# Beta24_mix.net
KiCad netlist of a schematic drawn in EAGLE
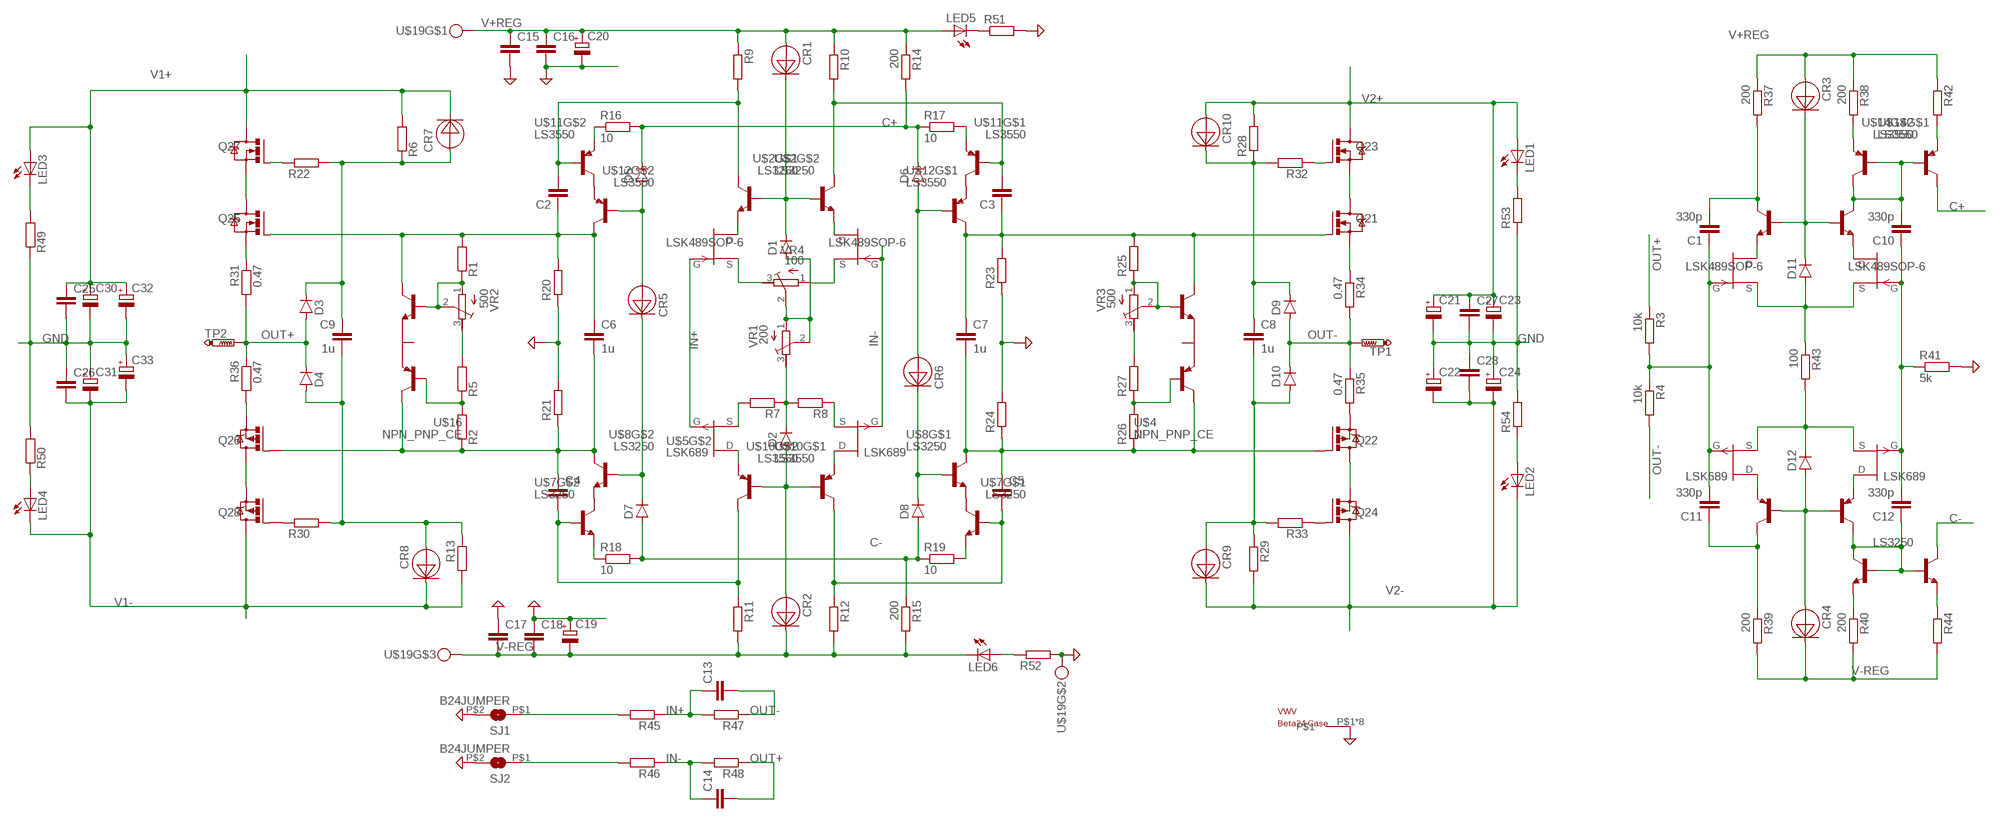
[diagram p0: schematic, sheet 1]
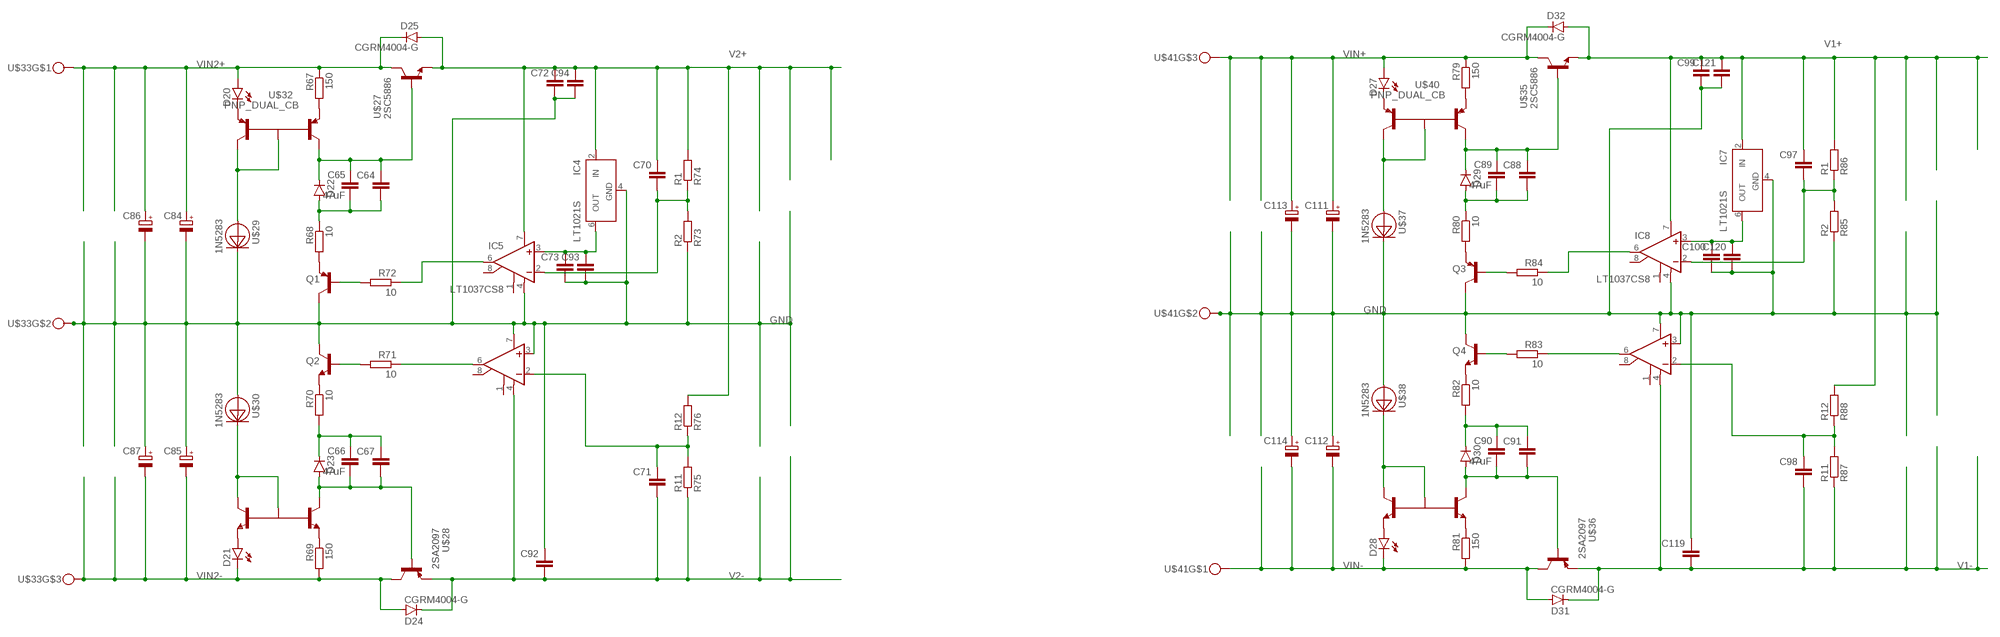
[diagram p1: schematic, sheet 2]

(export (version "E")
  (design (tool "Eeschema 10.0.6"))
  (components
    (comp (ref "C64")
      (value "C-EUC0805")
      (footprint "eagle-import:C0805")
      (libsource (lib "eagle-import") (part "C-EUC0805"))
    )
    (comp (ref "C65")
      (value "47uF")
      (footprint "eagle-import:C1206")
      (libsource (lib "eagle-import") (part "C-EUC1206"))
    )
    (comp (ref "C66")
      (value "47uF")
      (footprint "eagle-import:C1206")
      (libsource (lib "eagle-import") (part "C-EUC1206"))
    )
    (comp (ref "C67")
      (value "C-EUC0805")
      (footprint "eagle-import:C0805")
      (libsource (lib "eagle-import") (part "C-EUC0805"))
    )
    (comp (ref "C70")
      (value "C-EUC0805")
      (footprint "eagle-import:C0805")
      (libsource (lib "eagle-import") (part "C-EUC0805"))
    )
    (comp (ref "C71")
      (value "C-EUC0805")
      (footprint "eagle-import:C0805")
      (libsource (lib "eagle-import") (part "C-EUC0805"))
    )
    (comp (ref "C72")
      (value "C-EUC0805")
      (footprint "eagle-import:C0805")
      (libsource (lib "eagle-import") (part "C-EUC0805"))
    )
    (comp (ref "C73")
      (value "C-EUC0805")
      (footprint "eagle-import:C0805")
      (libsource (lib "eagle-import") (part "C-EUC0805"))
    )
    (comp (ref "C84")
      (value "CPOL-EUG")
      (footprint "eagle-import:PANASONIC_G")
      (libsource (lib "eagle-import") (part "CPOL-EUG"))
    )
    (comp (ref "C85")
      (value "CPOL-EUG")
      (footprint "eagle-import:PANASONIC_G")
      (libsource (lib "eagle-import") (part "CPOL-EUG"))
    )
    (comp (ref "C86")
      (value "CPOL-EUG")
      (footprint "eagle-import:PANASONIC_G")
      (libsource (lib "eagle-import") (part "CPOL-EUG"))
    )
    (comp (ref "C87")
      (value "CPOL-EUG")
      (footprint "eagle-import:PANASONIC_G")
      (libsource (lib "eagle-import") (part "CPOL-EUG"))
    )
    (comp (ref "C88")
      (value "C-EUC0805")
      (footprint "eagle-import:C0805")
      (libsource (lib "eagle-import") (part "C-EUC0805"))
    )
    (comp (ref "C89")
      (value "47uF")
      (footprint "eagle-import:C1206")
      (libsource (lib "eagle-import") (part "C-EUC1206"))
    )
    (comp (ref "C90")
      (value "47uF")
      (footprint "eagle-import:C1206")
      (libsource (lib "eagle-import") (part "C-EUC1206"))
    )
    (comp (ref "C91")
      (value "C-EUC0805")
      (footprint "eagle-import:C0805")
      (libsource (lib "eagle-import") (part "C-EUC0805"))
    )
    (comp (ref "C92")
      (value "C-EUC0805")
      (footprint "eagle-import:C0805")
      (libsource (lib "eagle-import") (part "C-EUC0805"))
    )
    (comp (ref "C93")
      (value "C-EUC0805")
      (footprint "eagle-import:C0805")
      (libsource (lib "eagle-import") (part "C-EUC0805"))
    )
    (comp (ref "C94")
      (value "C-EUC0805")
      (footprint "eagle-import:C0805")
      (libsource (lib "eagle-import") (part "C-EUC0805"))
    )
    (comp (ref "C97")
      (value "C-EUC0805")
      (footprint "eagle-import:C0805")
      (libsource (lib "eagle-import") (part "C-EUC0805"))
    )
    (comp (ref "C98")
      (value "C-EUC0805")
      (footprint "eagle-import:C0805")
      (libsource (lib "eagle-import") (part "C-EUC0805"))
    )
    (comp (ref "C99")
      (value "C-EUC0805")
      (footprint "eagle-import:C0805")
      (libsource (lib "eagle-import") (part "C-EUC0805"))
    )
    (comp (ref "C100")
      (value "C-EUC0805")
      (footprint "eagle-import:C0805")
      (libsource (lib "eagle-import") (part "C-EUC0805"))
    )
    (comp (ref "C111")
      (value "CPOL-EUG")
      (footprint "eagle-import:PANASONIC_G")
      (libsource (lib "eagle-import") (part "CPOL-EUG"))
    )
    (comp (ref "C112")
      (value "CPOL-EUG")
      (footprint "eagle-import:PANASONIC_G")
      (libsource (lib "eagle-import") (part "CPOL-EUG"))
    )
    (comp (ref "C113")
      (value "CPOL-EUG")
      (footprint "eagle-import:PANASONIC_G")
      (libsource (lib "eagle-import") (part "CPOL-EUG"))
    )
    (comp (ref "C114")
      (value "CPOL-EUG")
      (footprint "eagle-import:PANASONIC_G")
      (libsource (lib "eagle-import") (part "CPOL-EUG"))
    )
    (comp (ref "C119")
      (value "C-EUC0805")
      (footprint "eagle-import:C0805")
      (libsource (lib "eagle-import") (part "C-EUC0805"))
    )
    (comp (ref "C120")
      (value "C-EUC0805")
      (footprint "eagle-import:C0805")
      (libsource (lib "eagle-import") (part "C-EUC0805"))
    )
    (comp (ref "C121")
      (value "C-EUC0805")
      (footprint "eagle-import:C0805")
      (libsource (lib "eagle-import") (part "C-EUC0805"))
    )
    (comp (ref "D20")
      (value "LEDVWV1206")
      (footprint "eagle-import:LED_SML1206")
      (libsource (lib "eagle-import") (part "LEDVWV1206"))
    )
    (comp (ref "D21")
      (value "LEDVWV1206")
      (footprint "eagle-import:LED_SML1206")
      (libsource (lib "eagle-import") (part "LEDVWV1206"))
    )
    (comp (ref "D22")
      (value "TZMC10")
      (footprint "eagle-import:SOD80C")
      (libsource (lib "eagle-import") (part "DIODE-SOD80C"))
    )
    (comp (ref "D23")
      (value "TZAMC10")
      (footprint "eagle-import:SOD80C")
      (libsource (lib "eagle-import") (part "DIODE-SOD80C"))
    )
    (comp (ref "D24")
      (value "CGRM4004-G")
      (footprint "eagle-import:SOD-123_MINI-SMA")
      (libsource (lib "eagle-import") (part "CGRM400-G4"))
    )
    (comp (ref "D25")
      (value "CGRM4004-G")
      (footprint "eagle-import:SOD-123_MINI-SMA")
      (libsource (lib "eagle-import") (part "CGRM400-G4"))
    )
    (comp (ref "D27")
      (value "LEDVWV1206")
      (footprint "eagle-import:LED_SML1206")
      (libsource (lib "eagle-import") (part "LEDVWV1206"))
    )
    (comp (ref "D28")
      (value "LEDVWV1206")
      (footprint "eagle-import:LED_SML1206")
      (libsource (lib "eagle-import") (part "LEDVWV1206"))
    )
    (comp (ref "D29")
      (value "TZMC10")
      (footprint "eagle-import:SOD80C")
      (libsource (lib "eagle-import") (part "DIODE-SOD80C"))
    )
    (comp (ref "D30")
      (value "TZAMC10")
      (footprint "eagle-import:SOD80C")
      (libsource (lib "eagle-import") (part "DIODE-SOD80C"))
    )
    (comp (ref "D31")
      (value "CGRM4004-G")
      (footprint "eagle-import:SOD-123_MINI-SMA")
      (libsource (lib "eagle-import") (part "CGRM400-G4"))
    )
    (comp (ref "D32")
      (value "CGRM4004-G")
      (footprint "eagle-import:SOD-123_MINI-SMA")
      (libsource (lib "eagle-import") (part "CGRM400-G4"))
    )
    (comp (ref "IC4")
      (value "LT1021S")
      (footprint "eagle-import:SOIC8")
      (fields (field (name "MPN") "LT1021DCS8-10#PBF"))
      (libsource (lib "eagle-import") (part "LT1021S"))
    )
    (comp (ref "IC5")
      (value "LT1037CS8")
      (footprint "eagle-import:SOIC8")
      (libsource (lib "eagle-import") (part "LT10S837C"))
    )
    (comp (ref "IC6")
      (value "LT1037CS8")
      (footprint "eagle-import:SOIC8")
      (libsource (lib "eagle-import") (part "LT10S837C"))
    )
    (comp (ref "IC7")
      (value "LT1021S")
      (footprint "eagle-import:SOIC8")
      (fields (field (name "MPN") "LT1021DCS8-10#PBF"))
      (libsource (lib "eagle-import") (part "LT1021S"))
    )
    (comp (ref "IC8")
      (value "LT1037CS8")
      (footprint "eagle-import:SOIC8")
      (libsource (lib "eagle-import") (part "LT10S837C"))
    )
    (comp (ref "IC9")
      (value "LT1037CS8")
      (footprint "eagle-import:SOIC8")
      (libsource (lib "eagle-import") (part "LT10S837C"))
    )
    (comp (ref "Q1")
      (value "TRANSISTOR_BC857C-PNP-SOT23-BEC")
      (footprint "eagle-import:TRANSISTOR_SOT23-BEC")
      (libsource (lib "eagle-import") (part "TRANSISTOR_-PNP-SOT23-BECBC857C"))
    )
    (comp (ref "Q2")
      (value "TRANSISTOR_BC847CLT1-NPN-SOT23-BEC")
      (footprint "eagle-import:TRANSISTOR_SOT23-BEC")
      (libsource (lib "eagle-import") (part "TRANSISTOR_-NPN-SOT23-BECBC847CLT1"))
    )
    (comp (ref "Q3")
      (value "TRANSISTOR_BC857C-PNP-SOT23-BEC")
      (footprint "eagle-import:TRANSISTOR_SOT23-BEC")
      (libsource (lib "eagle-import") (part "TRANSISTOR_-PNP-SOT23-BECBC857C"))
    )
    (comp (ref "Q4")
      (value "TRANSISTOR_BC847CLT1-NPN-SOT23-BEC")
      (footprint "eagle-import:TRANSISTOR_SOT23-BEC")
      (libsource (lib "eagle-import") (part "TRANSISTOR_-NPN-SOT23-BECBC847CLT1"))
    )
    (comp (ref "R67")
      (value "150")
      (footprint "eagle-import:MINI_MELF-0204W")
      (libsource (lib "eagle-import") (part "R-EU_MELF0204W"))
    )
    (comp (ref "R68")
      (value "10")
      (footprint "eagle-import:MINI_MELF-0204W")
      (libsource (lib "eagle-import") (part "R-EU_MELF0204W"))
    )
    (comp (ref "R69")
      (value "150")
      (footprint "eagle-import:MINI_MELF-0204W")
      (libsource (lib "eagle-import") (part "R-EU_MELF0204W"))
    )
    (comp (ref "R70")
      (value "10")
      (footprint "eagle-import:MINI_MELF-0204W")
      (libsource (lib "eagle-import") (part "R-EU_MELF0204W"))
    )
    (comp (ref "R71")
      (value "10")
      (footprint "eagle-import:MINI_MELF-0204W")
      (libsource (lib "eagle-import") (part "R-EU_MELF0204W"))
    )
    (comp (ref "R72")
      (value "10")
      (footprint "eagle-import:MINI_MELF-0204W")
      (libsource (lib "eagle-import") (part "R-EU_MELF0204W"))
    )
    (comp (ref "R73")
      (value "R2")
      (footprint "eagle-import:MINI_MELF-0204W")
      (libsource (lib "eagle-import") (part "R-EU_MELF0204W"))
    )
    (comp (ref "R74")
      (value "R1")
      (footprint "eagle-import:MINI_MELF-0204W")
      (libsource (lib "eagle-import") (part "R-EU_MELF0204W"))
    )
    (comp (ref "R75")
      (value "R11")
      (footprint "eagle-import:MINI_MELF-0204W")
      (libsource (lib "eagle-import") (part "R-EU_MELF0204W"))
    )
    (comp (ref "R76")
      (value "R12")
      (footprint "eagle-import:MINI_MELF-0204W")
      (libsource (lib "eagle-import") (part "R-EU_MELF0204W"))
    )
    (comp (ref "R79")
      (value "150")
      (footprint "eagle-import:MINI_MELF-0204W")
      (libsource (lib "eagle-import") (part "R-EU_MELF0204W"))
    )
    (comp (ref "R80")
      (value "10")
      (footprint "eagle-import:MINI_MELF-0204W")
      (libsource (lib "eagle-import") (part "R-EU_MELF0204W"))
    )
    (comp (ref "R81")
      (value "150")
      (footprint "eagle-import:MINI_MELF-0204W")
      (libsource (lib "eagle-import") (part "R-EU_MELF0204W"))
    )
    (comp (ref "R82")
      (value "10")
      (footprint "eagle-import:MINI_MELF-0204W")
      (libsource (lib "eagle-import") (part "R-EU_MELF0204W"))
    )
    (comp (ref "R83")
      (value "10")
      (footprint "eagle-import:MINI_MELF-0204W")
      (libsource (lib "eagle-import") (part "R-EU_MELF0204W"))
    )
    (comp (ref "R84")
      (value "10")
      (footprint "eagle-import:MINI_MELF-0204W")
      (libsource (lib "eagle-import") (part "R-EU_MELF0204W"))
    )
    (comp (ref "R85")
      (value "R2")
      (footprint "eagle-import:MINI_MELF-0204W")
      (libsource (lib "eagle-import") (part "R-EU_MELF0204W"))
    )
    (comp (ref "R86")
      (value "R1")
      (footprint "eagle-import:MINI_MELF-0204W")
      (libsource (lib "eagle-import") (part "R-EU_MELF0204W"))
    )
    (comp (ref "R87")
      (value "R11")
      (footprint "eagle-import:MINI_MELF-0204W")
      (libsource (lib "eagle-import") (part "R-EU_MELF0204W"))
    )
    (comp (ref "R88")
      (value "R12")
      (footprint "eagle-import:MINI_MELF-0204W")
      (libsource (lib "eagle-import") (part "R-EU_MELF0204W"))
    )
    (comp (ref "U$27")
      (value "2SC5886")
      (footprint "eagle-import:NEW-PWMOLD")
      (libsource (lib "eagle-import") (part "2SC5886"))
    )
    (comp (ref "U$28")
      (value "2SA2097")
      (footprint "eagle-import:NEW-PWMOLD")
      (libsource (lib "eagle-import") (part "2SA2097"))
    )
    (comp (ref "U$29")
      (value "1N5283")
      (footprint "eagle-import:SMD")
      (libsource (lib "eagle-import") (part "1N5283"))
    )
    (comp (ref "U$30")
      (value "1N5283")
      (footprint "eagle-import:SMD")
      (libsource (lib "eagle-import") (part "1N5283"))
    )
    (comp (ref "U$31")
      (value "NPN_DUAL_CBSOT-25-5")
      (footprint "eagle-import:SOT25")
      (libsource (lib "eagle-import") (part "NPN_DUAL_CBSOT-25-5"))
    )
    (comp (ref "U$32")
      (value "PNP_DUAL_CB")
      (footprint "eagle-import:SOT25")
      (libsource (lib "eagle-import") (part "PNP_DUAL_CB"))
    )
    (comp (ref "U$33")
      (value "CON-PTSM-3")
      (footprint "eagle-import:CON-PTSM-3")
      (libsource (lib "eagle-import") (part "CON-PTSM-3"))
    )
    (comp (ref "U$35")
      (value "2SC5886")
      (footprint "eagle-import:NEW-PWMOLD")
      (libsource (lib "eagle-import") (part "2SC5886"))
    )
    (comp (ref "U$36")
      (value "2SA2097")
      (footprint "eagle-import:NEW-PWMOLD")
      (libsource (lib "eagle-import") (part "2SA2097"))
    )
    (comp (ref "U$37")
      (value "1N5283")
      (footprint "eagle-import:SMD")
      (libsource (lib "eagle-import") (part "1N5283"))
    )
    (comp (ref "U$38")
      (value "1N5283")
      (footprint "eagle-import:SMD")
      (libsource (lib "eagle-import") (part "1N5283"))
    )
    (comp (ref "U$39")
      (value "NPN_DUAL_CBSOT-25-5")
      (footprint "eagle-import:SOT25")
      (libsource (lib "eagle-import") (part "NPN_DUAL_CBSOT-25-5"))
    )
    (comp (ref "U$40")
      (value "PNP_DUAL_CB")
      (footprint "eagle-import:SOT25")
      (libsource (lib "eagle-import") (part "PNP_DUAL_CB"))
    )
    (comp (ref "U$41")
      (value "CON-PTSM-3")
      (footprint "eagle-import:CON-PTSM-3")
      (libsource (lib "eagle-import") (part "CON-PTSM-3"))
    )
    (comp (ref "C1")
      (value "330p")
      (footprint "eagle-import:C1206")
      (libsource (lib "eagle-import") (part "C-EUC1206"))
    )
    (comp (ref "C2")
      (value "C-EUC1206")
      (footprint "eagle-import:C1206")
      (libsource (lib "eagle-import") (part "C-EUC1206"))
    )
    (comp (ref "C3")
      (value "C-EUC1206")
      (footprint "eagle-import:C1206")
      (libsource (lib "eagle-import") (part "C-EUC1206"))
    )
    (comp (ref "C4")
      (value "C-EUC1206")
      (footprint "eagle-import:C1206")
      (libsource (lib "eagle-import") (part "C-EUC1206"))
    )
    (comp (ref "C5")
      (value "C-EUC1206")
      (footprint "eagle-import:C1206")
      (libsource (lib "eagle-import") (part "C-EUC1206"))
    )
    (comp (ref "C6")
      (value "1u")
      (footprint "eagle-import:C1210")
      (libsource (lib "eagle-import") (part "C-EUC1210"))
    )
    (comp (ref "C7")
      (value "1u")
      (footprint "eagle-import:C1210")
      (libsource (lib "eagle-import") (part "C-EUC1210"))
    )
    (comp (ref "C8")
      (value "1u")
      (footprint "eagle-import:C1206")
      (libsource (lib "eagle-import") (part "C-EUC1206"))
    )
    (comp (ref "C9")
      (value "1u")
      (footprint "eagle-import:C1206")
      (libsource (lib "eagle-import") (part "C-EUC1206"))
    )
    (comp (ref "C10")
      (value "330p")
      (footprint "eagle-import:C1206")
      (libsource (lib "eagle-import") (part "C-EUC1206"))
    )
    (comp (ref "C11")
      (value "330p")
      (footprint "eagle-import:C1206")
      (libsource (lib "eagle-import") (part "C-EUC1206"))
    )
    (comp (ref "C12")
      (value "330p")
      (footprint "eagle-import:C1206")
      (libsource (lib "eagle-import") (part "C-EUC1206"))
    )
    (comp (ref "C13")
      (value "C-EUC1206")
      (footprint "eagle-import:C1206")
      (libsource (lib "eagle-import") (part "C-EUC1206"))
    )
    (comp (ref "C14")
      (value "C-EUC1206")
      (footprint "eagle-import:C1206")
      (libsource (lib "eagle-import") (part "C-EUC1206"))
    )
    (comp (ref "C15")
      (value "C-EUC1206")
      (footprint "eagle-import:C1206")
      (libsource (lib "eagle-import") (part "C-EUC1206"))
    )
    (comp (ref "C16")
      (value "C-EUC1206")
      (footprint "eagle-import:C1206")
      (libsource (lib "eagle-import") (part "C-EUC1206"))
    )
    (comp (ref "C17")
      (value "C-EUC1206")
      (footprint "eagle-import:C1206")
      (libsource (lib "eagle-import") (part "C-EUC1206"))
    )
    (comp (ref "C18")
      (value "C-EUC1206")
      (footprint "eagle-import:C1206")
      (libsource (lib "eagle-import") (part "C-EUC1206"))
    )
    (comp (ref "C19")
      (value "CPOL-EUG")
      (footprint "eagle-import:PANASONIC_G")
      (libsource (lib "eagle-import") (part "CPOL-EUG"))
    )
    (comp (ref "C20")
      (value "CPOL-EUG")
      (footprint "eagle-import:PANASONIC_G")
      (libsource (lib "eagle-import") (part "CPOL-EUG"))
    )
    (comp (ref "C21")
      (value "CPOL-EUG")
      (footprint "eagle-import:PANASONIC_G")
      (libsource (lib "eagle-import") (part "CPOL-EUG"))
    )
    (comp (ref "C22")
      (value "CPOL-EUG")
      (footprint "eagle-import:PANASONIC_G")
      (libsource (lib "eagle-import") (part "CPOL-EUG"))
    )
    (comp (ref "C23")
      (value "CPOL-EUG")
      (footprint "eagle-import:PANASONIC_G")
      (libsource (lib "eagle-import") (part "CPOL-EUG"))
    )
    (comp (ref "C24")
      (value "CPOL-EUG")
      (footprint "eagle-import:PANASONIC_G")
      (libsource (lib "eagle-import") (part "CPOL-EUG"))
    )
    (comp (ref "C25")
      (value "C-EUC1206")
      (footprint "eagle-import:C1206")
      (libsource (lib "eagle-import") (part "C-EUC1206"))
    )
    (comp (ref "C26")
      (value "C-EUC1206")
      (footprint "eagle-import:C1206")
      (libsource (lib "eagle-import") (part "C-EUC1206"))
    )
    (comp (ref "C27")
      (value "C-EUC1206")
      (footprint "eagle-import:C1206")
      (libsource (lib "eagle-import") (part "C-EUC1206"))
    )
    (comp (ref "C28")
      (value "C-EUC1206")
      (footprint "eagle-import:C1206")
      (libsource (lib "eagle-import") (part "C-EUC1206"))
    )
    (comp (ref "C30")
      (value "CPOL-EUG")
      (footprint "eagle-import:PANASONIC_G")
      (libsource (lib "eagle-import") (part "CPOL-EUG"))
    )
    (comp (ref "C31")
      (value "CPOL-EUG")
      (footprint "eagle-import:PANASONIC_G")
      (libsource (lib "eagle-import") (part "CPOL-EUG"))
    )
    (comp (ref "C32")
      (value "CPOL-EUG")
      (footprint "eagle-import:PANASONIC_G")
      (libsource (lib "eagle-import") (part "CPOL-EUG"))
    )
    (comp (ref "C33")
      (value "CPOL-EUG")
      (footprint "eagle-import:PANASONIC_G")
      (libsource (lib "eagle-import") (part "CPOL-EUG"))
    )
    (comp (ref "CR1")
      (value "1N5283")
      (footprint "eagle-import:SMD")
      (libsource (lib "eagle-import") (part "1N5283"))
    )
    (comp (ref "CR2")
      (value "1N5283")
      (footprint "eagle-import:SMD")
      (libsource (lib "eagle-import") (part "1N5283"))
    )
    (comp (ref "CR3")
      (value "1N5283")
      (footprint "eagle-import:SMD")
      (libsource (lib "eagle-import") (part "1N5283"))
    )
    (comp (ref "CR4")
      (value "1N5283")
      (footprint "eagle-import:SMD")
      (libsource (lib "eagle-import") (part "1N5283"))
    )
    (comp (ref "CR5")
      (value "1N5283")
      (footprint "eagle-import:SMD")
      (libsource (lib "eagle-import") (part "1N5283"))
    )
    (comp (ref "CR6")
      (value "1N5283")
      (footprint "eagle-import:SMD")
      (libsource (lib "eagle-import") (part "1N5283"))
    )
    (comp (ref "CR7")
      (value "1N5283")
      (footprint "eagle-import:SMD")
      (libsource (lib "eagle-import") (part "1N5283"))
    )
    (comp (ref "CR8")
      (value "1N5283")
      (footprint "eagle-import:SMD")
      (libsource (lib "eagle-import") (part "1N5283"))
    )
    (comp (ref "CR9")
      (value "1N5283")
      (footprint "eagle-import:SMD")
      (libsource (lib "eagle-import") (part "1N5283"))
    )
    (comp (ref "CR10")
      (value "1N5283")
      (footprint "eagle-import:SMD")
      (libsource (lib "eagle-import") (part "1N5283"))
    )
    (comp (ref "D1")
      (value "DIODE-SOD80C")
      (footprint "eagle-import:SOD80C")
      (libsource (lib "eagle-import") (part "DIODE-SOD80C"))
    )
    (comp (ref "D2")
      (value "DIODE-SOD80C")
      (footprint "eagle-import:SOD80C")
      (libsource (lib "eagle-import") (part "DIODE-SOD80C"))
    )
    (comp (ref "D3")
      (value "DIODE-SOD80C")
      (footprint "eagle-import:SOD80C")
      (libsource (lib "eagle-import") (part "DIODE-SOD80C"))
    )
    (comp (ref "D4")
      (value "DIODE-SOD80C")
      (footprint "eagle-import:SOD80C")
      (libsource (lib "eagle-import") (part "DIODE-SOD80C"))
    )
    (comp (ref "D5")
      (value "DIODE-SOD80C")
      (footprint "eagle-import:SOD80C")
      (libsource (lib "eagle-import") (part "DIODE-SOD80C"))
    )
    (comp (ref "D6")
      (value "DIODE-SOD80C")
      (footprint "eagle-import:SOD80C")
      (libsource (lib "eagle-import") (part "DIODE-SOD80C"))
    )
    (comp (ref "D7")
      (value "DIODE-SOD80C")
      (footprint "eagle-import:SOD80C")
      (libsource (lib "eagle-import") (part "DIODE-SOD80C"))
    )
    (comp (ref "D8")
      (value "DIODE-SOD80C")
      (footprint "eagle-import:SOD80C")
      (libsource (lib "eagle-import") (part "DIODE-SOD80C"))
    )
    (comp (ref "D9")
      (value "DIODE-SOD80C")
      (footprint "eagle-import:SOD80C")
      (libsource (lib "eagle-import") (part "DIODE-SOD80C"))
    )
    (comp (ref "D10")
      (value "DIODE-SOD80C")
      (footprint "eagle-import:SOD80C")
      (libsource (lib "eagle-import") (part "DIODE-SOD80C"))
    )
    (comp (ref "D11")
      (value "DIODE-SOD80C")
      (footprint "eagle-import:SOD80C")
      (libsource (lib "eagle-import") (part "DIODE-SOD80C"))
    )
    (comp (ref "D12")
      (value "DIODE-SOD80C")
      (footprint "eagle-import:SOD80C")
      (libsource (lib "eagle-import") (part "DIODE-SOD80C"))
    )
    (comp (ref "LED1")
      (value "LED_LEDSML1206")
      (footprint "eagle-import:LED_SML1206")
      (libsource (lib "eagle-import") (part "LED_LEDSML1206"))
    )
    (comp (ref "LED2")
      (value "LED_LEDSML1206")
      (footprint "eagle-import:LED_SML1206")
      (libsource (lib "eagle-import") (part "LED_LEDSML1206"))
    )
    (comp (ref "LED3")
      (value "LED_LEDSML1206")
      (footprint "eagle-import:LED_SML1206")
      (libsource (lib "eagle-import") (part "LED_LEDSML1206"))
    )
    (comp (ref "LED4")
      (value "LED_LEDSML1206")
      (footprint "eagle-import:LED_SML1206")
      (libsource (lib "eagle-import") (part "LED_LEDSML1206"))
    )
    (comp (ref "LED5")
      (value "LED_LEDSML1206")
      (footprint "eagle-import:LED_SML1206")
      (libsource (lib "eagle-import") (part "LED_LEDSML1206"))
    )
    (comp (ref "LED6")
      (value "LED_LEDSML1206")
      (footprint "eagle-import:LED_SML1206")
      (libsource (lib "eagle-import") (part "LED_LEDSML1206"))
    )
    (comp (ref "Q21")
      (value "IRFZ24ND2PAK")
      (footprint "eagle-import:TO254P1054X240-3M")
      (libsource (lib "eagle-import") (part "IRFZ24ND2PAK"))
    )
    (comp (ref "Q22")
      (value "IRF9Z34D2PAK")
      (footprint "eagle-import:TO254P1054X240-3M")
      (libsource (lib "eagle-import") (part "IRF9Z34D2PAK"))
    )
    (comp (ref "Q23")
      (value "IRFZ24ND2PAK")
      (footprint "eagle-import:TO254P1054X240-3M")
      (libsource (lib "eagle-import") (part "IRFZ24ND2PAK"))
    )
    (comp (ref "Q24")
      (value "IRF9Z34D2PAK")
      (footprint "eagle-import:TO254P1054X240-3M")
      (libsource (lib "eagle-import") (part "IRF9Z34D2PAK"))
    )
    (comp (ref "Q25")
      (value "IRFZ24ND2PAK")
      (footprint "eagle-import:TO254P1054X240-3M")
      (libsource (lib "eagle-import") (part "IRFZ24ND2PAK"))
    )
    (comp (ref "Q26")
      (value "IRF9Z34D2PAK")
      (footprint "eagle-import:TO254P1054X240-3M")
      (libsource (lib "eagle-import") (part "IRF9Z34D2PAK"))
    )
    (comp (ref "Q27")
      (value "IRFZ24ND2PAK")
      (footprint "eagle-import:TO254P1054X240-3M")
      (libsource (lib "eagle-import") (part "IRFZ24ND2PAK"))
    )
    (comp (ref "Q28")
      (value "IRF9Z34D2PAK")
      (footprint "eagle-import:TO254P1054X240-3M")
      (libsource (lib "eagle-import") (part "IRF9Z34D2PAK"))
    )
    (comp (ref "R1")
      (value "R-EU_MELF0204W")
      (footprint "eagle-import:MINI_MELF-0204W")
      (libsource (lib "eagle-import") (part "R-EU_MELF0204W"))
    )
    (comp (ref "R2")
      (value "R-EU_MELF0204W")
      (footprint "eagle-import:MINI_MELF-0204W")
      (libsource (lib "eagle-import") (part "R-EU_MELF0204W"))
    )
    (comp (ref "R3")
      (value "10k")
      (footprint "eagle-import:MINI_MELF-0204W")
      (libsource (lib "eagle-import") (part "R-EU_MELF0204W"))
    )
    (comp (ref "R4")
      (value "10k")
      (footprint "eagle-import:MINI_MELF-0204W")
      (libsource (lib "eagle-import") (part "R-EU_MELF0204W"))
    )
    (comp (ref "R5")
      (value "R-EU_MELF0204W")
      (footprint "eagle-import:MINI_MELF-0204W")
      (libsource (lib "eagle-import") (part "R-EU_MELF0204W"))
    )
    (comp (ref "R6")
      (value "R-EU_MELF0204W")
      (footprint "eagle-import:MINI_MELF-0204W")
      (libsource (lib "eagle-import") (part "R-EU_MELF0204W"))
    )
    (comp (ref "R7")
      (value "R-EU_MELF0204W")
      (footprint "eagle-import:MINI_MELF-0204W")
      (libsource (lib "eagle-import") (part "R-EU_MELF0204W"))
    )
    (comp (ref "R8")
      (value "R-EU_MELF0204W")
      (footprint "eagle-import:MINI_MELF-0204W")
      (libsource (lib "eagle-import") (part "R-EU_MELF0204W"))
    )
    (comp (ref "R9")
      (value "R-EU_MELF0204W")
      (footprint "eagle-import:MINI_MELF-0204W")
      (libsource (lib "eagle-import") (part "R-EU_MELF0204W"))
    )
    (comp (ref "R10")
      (value "R-EU_MELF0204W")
      (footprint "eagle-import:MINI_MELF-0204W")
      (libsource (lib "eagle-import") (part "R-EU_MELF0204W"))
    )
    (comp (ref "R11")
      (value "R-EU_MELF0204W")
      (footprint "eagle-import:MINI_MELF-0204W")
      (libsource (lib "eagle-import") (part "R-EU_MELF0204W"))
    )
    (comp (ref "R12")
      (value "R-EU_MELF0204W")
      (footprint "eagle-import:MINI_MELF-0204W")
      (libsource (lib "eagle-import") (part "R-EU_MELF0204W"))
    )
    (comp (ref "R13")
      (value "R-EU_MELF0204W")
      (footprint "eagle-import:MINI_MELF-0204W")
      (libsource (lib "eagle-import") (part "R-EU_MELF0204W"))
    )
    (comp (ref "R14")
      (value "200")
      (footprint "eagle-import:MINI_MELF-0204W")
      (libsource (lib "eagle-import") (part "R-EU_MELF0204W"))
    )
    (comp (ref "R15")
      (value "200")
      (footprint "eagle-import:MINI_MELF-0204W")
      (libsource (lib "eagle-import") (part "R-EU_MELF0204W"))
    )
    (comp (ref "R16")
      (value "10")
      (footprint "eagle-import:MINI_MELF-0204W")
      (libsource (lib "eagle-import") (part "R-EU_MELF0204W"))
    )
    (comp (ref "R17")
      (value "10")
      (footprint "eagle-import:MINI_MELF-0204W")
      (libsource (lib "eagle-import") (part "R-EU_MELF0204W"))
    )
    (comp (ref "R18")
      (value "10")
      (footprint "eagle-import:MINI_MELF-0204W")
      (libsource (lib "eagle-import") (part "R-EU_MELF0204W"))
    )
    (comp (ref "R19")
      (value "10")
      (footprint "eagle-import:MINI_MELF-0204W")
      (libsource (lib "eagle-import") (part "R-EU_MELF0204W"))
    )
    (comp (ref "R20")
      (value "R-EU_MELF0204W")
      (footprint "eagle-import:MINI_MELF-0204W")
      (libsource (lib "eagle-import") (part "R-EU_MELF0204W"))
    )
    (comp (ref "R21")
      (value "R-EU_MELF0204W")
      (footprint "eagle-import:MINI_MELF-0204W")
      (libsource (lib "eagle-import") (part "R-EU_MELF0204W"))
    )
    (comp (ref "R22")
      (value "R-EU_MELF0204W")
      (footprint "eagle-import:MINI_MELF-0204W")
      (libsource (lib "eagle-import") (part "R-EU_MELF0204W"))
    )
    (comp (ref "R23")
      (value "R-EU_MELF0204W")
      (footprint "eagle-import:MINI_MELF-0204W")
      (libsource (lib "eagle-import") (part "R-EU_MELF0204W"))
    )
    (comp (ref "R24")
      (value "R-EU_MELF0204W")
      (footprint "eagle-import:MINI_MELF-0204W")
      (libsource (lib "eagle-import") (part "R-EU_MELF0204W"))
    )
    (comp (ref "R25")
      (value "R-EU_MELF0204W")
      (footprint "eagle-import:MINI_MELF-0204W")
      (libsource (lib "eagle-import") (part "R-EU_MELF0204W"))
    )
    (comp (ref "R26")
      (value "R-EU_MELF0204W")
      (footprint "eagle-import:MINI_MELF-0204W")
      (libsource (lib "eagle-import") (part "R-EU_MELF0204W"))
    )
    (comp (ref "R27")
      (value "R-EU_MELF0204W")
      (footprint "eagle-import:MINI_MELF-0204W")
      (libsource (lib "eagle-import") (part "R-EU_MELF0204W"))
    )
    (comp (ref "R28")
      (value "R-EU_MELF0204W")
      (footprint "eagle-import:MINI_MELF-0204W")
      (libsource (lib "eagle-import") (part "R-EU_MELF0204W"))
    )
    (comp (ref "R29")
      (value "R-EU_MELF0204W")
      (footprint "eagle-import:MINI_MELF-0204W")
      (libsource (lib "eagle-import") (part "R-EU_MELF0204W"))
    )
    (comp (ref "R30")
      (value "R-EU_MELF0204W")
      (footprint "eagle-import:MINI_MELF-0204W")
      (libsource (lib "eagle-import") (part "R-EU_MELF0204W"))
    )
    (comp (ref "R31")
      (value "0.47")
      (footprint "eagle-import:R2512")
      (libsource (lib "eagle-import") (part "R-EU_R2512"))
    )
    (comp (ref "R32")
      (value "R-EU_MELF0204W")
      (footprint "eagle-import:MINI_MELF-0204W")
      (libsource (lib "eagle-import") (part "R-EU_MELF0204W"))
    )
    (comp (ref "R33")
      (value "R-EU_MELF0204W")
      (footprint "eagle-import:MINI_MELF-0204W")
      (libsource (lib "eagle-import") (part "R-EU_MELF0204W"))
    )
    (comp (ref "R34")
      (value "0.47")
      (footprint "eagle-import:R2512")
      (libsource (lib "eagle-import") (part "R-EU_R2512"))
    )
    (comp (ref "R35")
      (value "0.47")
      (footprint "eagle-import:R2512")
      (libsource (lib "eagle-import") (part "R-EU_R2512"))
    )
    (comp (ref "R36")
      (value "0.47")
      (footprint "eagle-import:R2512")
      (libsource (lib "eagle-import") (part "R-EU_R2512"))
    )
    (comp (ref "R37")
      (value "200")
      (footprint "eagle-import:MINI_MELF-0204W")
      (libsource (lib "eagle-import") (part "R-EU_MELF0204W"))
    )
    (comp (ref "R38")
      (value "200")
      (footprint "eagle-import:MINI_MELF-0204W")
      (libsource (lib "eagle-import") (part "R-EU_MELF0204W"))
    )
    (comp (ref "R39")
      (value "200")
      (footprint "eagle-import:MINI_MELF-0204W")
      (libsource (lib "eagle-import") (part "R-EU_MELF0204W"))
    )
    (comp (ref "R40")
      (value "200")
      (footprint "eagle-import:MINI_MELF-0204W")
      (libsource (lib "eagle-import") (part "R-EU_MELF0204W"))
    )
    (comp (ref "R41")
      (value "5k")
      (footprint "eagle-import:MINI_MELF-0204W")
      (libsource (lib "eagle-import") (part "R-EU_MELF0204W"))
    )
    (comp (ref "R42")
      (value "R-EU_MELF0204W")
      (footprint "eagle-import:MINI_MELF-0204W")
      (libsource (lib "eagle-import") (part "R-EU_MELF0204W"))
    )
    (comp (ref "R43")
      (value "100")
      (footprint "eagle-import:MINI_MELF-0204W")
      (libsource (lib "eagle-import") (part "R-EU_MELF0204W"))
    )
    (comp (ref "R44")
      (value "R-EU_MELF0204W")
      (footprint "eagle-import:MINI_MELF-0204W")
      (libsource (lib "eagle-import") (part "R-EU_MELF0204W"))
    )
    (comp (ref "R45")
      (value "R-EU_MELF0204W")
      (footprint "eagle-import:MINI_MELF-0204W")
      (libsource (lib "eagle-import") (part "R-EU_MELF0204W"))
    )
    (comp (ref "R46")
      (value "R-EU_MELF0204W")
      (footprint "eagle-import:MINI_MELF-0204W")
      (libsource (lib "eagle-import") (part "R-EU_MELF0204W"))
    )
    (comp (ref "R47")
      (value "R-EU_MELF0204W")
      (footprint "eagle-import:MINI_MELF-0204W")
      (libsource (lib "eagle-import") (part "R-EU_MELF0204W"))
    )
    (comp (ref "R48")
      (value "R-EU_MELF0204W")
      (footprint "eagle-import:MINI_MELF-0204W")
      (libsource (lib "eagle-import") (part "R-EU_MELF0204W"))
    )
    (comp (ref "R49")
      (value "R-EU_MELF0204W")
      (footprint "eagle-import:MINI_MELF-0204W")
      (libsource (lib "eagle-import") (part "R-EU_MELF0204W"))
    )
    (comp (ref "R50")
      (value "R-EU_MELF0204W")
      (footprint "eagle-import:MINI_MELF-0204W")
      (libsource (lib "eagle-import") (part "R-EU_MELF0204W"))
    )
    (comp (ref "R51")
      (value "200")
      (footprint "eagle-import:MINI_MELF-0204W")
      (libsource (lib "eagle-import") (part "R-EU_MELF0204W"))
    )
    (comp (ref "R52")
      (value "R-EU_MELF0204W")
      (footprint "eagle-import:MINI_MELF-0204W")
      (libsource (lib "eagle-import") (part "R-EU_MELF0204W"))
    )
    (comp (ref "R53")
      (value "R-EU_MELF0204W")
      (footprint "eagle-import:MINI_MELF-0204W")
      (libsource (lib "eagle-import") (part "R-EU_MELF0204W"))
    )
    (comp (ref "R54")
      (value "R-EU_MELF0204W")
      (footprint "eagle-import:MINI_MELF-0204W")
      (libsource (lib "eagle-import") (part "R-EU_MELF0204W"))
    )
    (comp (ref "SJ1")
      (value "B24JUMPER")
      (footprint "eagle-import:B24J")
      (libsource (lib "eagle-import") (part "B24JUMPER"))
    )
    (comp (ref "SJ2")
      (value "B24JUMPER")
      (footprint "eagle-import:B24J")
      (libsource (lib "eagle-import") (part "B24JUMPER"))
    )
    (comp (ref "TP1")
      (value "PTR1PAD1-20")
      (footprint "eagle-import:P1-20")
      (libsource (lib "eagle-import") (part "PTR1PAD1-20"))
    )
    (comp (ref "TP2")
      (value "PTR1PAD1-20")
      (footprint "eagle-import:P1-20")
      (libsource (lib "eagle-import") (part "PTR1PAD1-20"))
    )
    (comp (ref "U$1")
      (value "LSK489SOP-6")
      (footprint "eagle-import:SOT-23-6")
      (libsource (lib "eagle-import") (part "LSK489SOP-6"))
    )
    (comp (ref "U$2")
      (value "LS3250")
      (footprint "eagle-import:SOT-23-6")
      (libsource (lib "eagle-import") (part "LS3250"))
    )
    (comp (ref "U$3")
      (value "LSK489SOP-6")
      (footprint "eagle-import:SOT-23-6")
      (libsource (lib "eagle-import") (part "LSK489SOP-6"))
    )
    (comp (ref "U$4")
      (value "NPN_PNP_CE")
      (footprint "eagle-import:SOT25")
      (libsource (lib "eagle-import") (part "NPN_PNP_CE"))
    )
    (comp (ref "U$5")
      (value "LSK689")
      (footprint "eagle-import:SOT-23-6")
      (libsource (lib "eagle-import") (part "LSK689"))
    )
    (comp (ref "U$6")
      (value "LS3250")
      (footprint "eagle-import:SOT-23-6")
      (libsource (lib "eagle-import") (part "LS3250"))
    )
    (comp (ref "U$7")
      (value "LS3250")
      (footprint "eagle-import:SOT-23-6")
      (libsource (lib "eagle-import") (part "LS3250"))
    )
    (comp (ref "U$8")
      (value "LS3250")
      (footprint "eagle-import:SOT-23-6")
      (libsource (lib "eagle-import") (part "LS3250"))
    )
    (comp (ref "U$9")
      (value "LS3550")
      (footprint "eagle-import:SOT-23-6")
      (libsource (lib "eagle-import") (part "LS3550"))
    )
    (comp (ref "U$10")
      (value "LS3550")
      (footprint "eagle-import:SOT-23-6")
      (libsource (lib "eagle-import") (part "LS3550"))
    )
    (comp (ref "U$11")
      (value "LS3550")
      (footprint "eagle-import:SOT-23-6")
      (libsource (lib "eagle-import") (part "LS3550"))
    )
    (comp (ref "U$12")
      (value "LS3550")
      (footprint "eagle-import:SOT-23-6")
      (libsource (lib "eagle-import") (part "LS3550"))
    )
    (comp (ref "U$13")
      (value "LS3250")
      (footprint "eagle-import:SOT-23-6")
      (libsource (lib "eagle-import") (part "LS3250"))
    )
    (comp (ref "U$14")
      (value "LS3550")
      (footprint "eagle-import:SOT-23-6")
      (libsource (lib "eagle-import") (part "LS3550"))
    )
    (comp (ref "U$15")
      (value "LSK689")
      (footprint "eagle-import:SOT-23-6")
      (libsource (lib "eagle-import") (part "LSK689"))
    )
    (comp (ref "U$16")
      (value "NPN_PNP_CE")
      (footprint "eagle-import:SOT25")
      (libsource (lib "eagle-import") (part "NPN_PNP_CE"))
    )
    (comp (ref "U$17")
      (value "VWV")
      (footprint "eagle-import:VWV")
      (libsource (lib "eagle-import") (part "VWV"))
    )
    (comp (ref "U$18")
      (value "B24C")
      (footprint "eagle-import:B24C")
      (libsource (lib "eagle-import") (part "B24C"))
    )
    (comp (ref "U$19")
      (value "CON-PTSM-3")
      (footprint "eagle-import:CON-PTSM-3")
      (libsource (lib "eagle-import") (part "CON-PTSM-3"))
    )
    (comp (ref "VR1")
      (value "200")
      (footprint "eagle-import:RTRIM3296W")
      (libsource (lib "eagle-import") (part "R-TRIMM3296W"))
    )
    (comp (ref "VR2")
      (value "500")
      (footprint "eagle-import:RTRIM3296W")
      (libsource (lib "eagle-import") (part "R-TRIMM3296W"))
    )
    (comp (ref "VR3")
      (value "500")
      (footprint "eagle-import:RTRIM3296W")
      (libsource (lib "eagle-import") (part "R-TRIMM3296W"))
    )
    (comp (ref "VR4")
      (value "100")
      (footprint "eagle-import:RTRIM3296W")
      (libsource (lib "eagle-import") (part "R-TRIMM3296W"))
    )
  )
  (nets
    (net (code "1") (name "C+") (class "Default")
      (node (ref "D5") (pin "C") (pinfunction "C_C") (pintype "passive"))
      (node (ref "D6") (pin "C") (pinfunction "C_C") (pintype "passive"))
      (node (ref "R14") (pin "2") (pinfunction "2_2") (pintype "passive"))
      (node (ref "R16") (pin "2") (pinfunction "2_2") (pintype "passive"))
      (node (ref "R17") (pin "1") (pinfunction "1_1") (pintype "passive"))
      (node (ref "U$14") (pin "6") (pinfunction "C_6") (pintype "passive"))
    )
    (net (code "2") (name "C-") (class "Default")
      (node (ref "D7") (pin "A") (pinfunction "A_A") (pintype "passive"))
      (node (ref "D8") (pin "A") (pinfunction "A_A") (pintype "passive"))
      (node (ref "R15") (pin "1") (pinfunction "1_1") (pintype "passive"))
      (node (ref "R18") (pin "2") (pinfunction "2_2") (pintype "passive"))
      (node (ref "R19") (pin "1") (pinfunction "1_1") (pintype "passive"))
      (node (ref "U$13") (pin "6") (pinfunction "C_6") (pintype "passive"))
    )
    (net (code "3") (name "GND") (class "Default")
      (node (ref "C100") (pin "2") (pinfunction "2_2") (pintype "passive"))
      (node (ref "C111") (pin "-") (pinfunction "-_-") (pintype "passive"))
      (node (ref "C112") (pin "+") (pinfunction "+_+") (pintype "passive"))
      (node (ref "C113") (pin "-") (pinfunction "-_-") (pintype "passive"))
      (node (ref "C114") (pin "+") (pinfunction "+_+") (pintype "passive"))
      (node (ref "C119") (pin "1") (pinfunction "1_1") (pintype "passive"))
      (node (ref "C120") (pin "2") (pinfunction "2_2") (pintype "passive"))
      (node (ref "C121") (pin "2") (pinfunction "2_2") (pintype "passive"))
      (node (ref "C15") (pin "2") (pinfunction "2_2") (pintype "passive"))
      (node (ref "C16") (pin "2") (pinfunction "2_2") (pintype "passive"))
      (node (ref "C17") (pin "1") (pinfunction "1_1") (pintype "passive"))
      (node (ref "C18") (pin "1") (pinfunction "1_1") (pintype "passive"))
      (node (ref "C19") (pin "+") (pinfunction "+_+") (pintype "passive"))
      (node (ref "C20") (pin "-") (pinfunction "-_-") (pintype "passive"))
      (node (ref "C21") (pin "-") (pinfunction "-_-") (pintype "passive"))
      (node (ref "C22") (pin "+") (pinfunction "+_+") (pintype "passive"))
      (node (ref "C23") (pin "-") (pinfunction "-_-") (pintype "passive"))
      (node (ref "C24") (pin "+") (pinfunction "+_+") (pintype "passive"))
      (node (ref "C25") (pin "2") (pinfunction "2_2") (pintype "passive"))
      (node (ref "C26") (pin "1") (pinfunction "1_1") (pintype "passive"))
      (node (ref "C27") (pin "2") (pinfunction "2_2") (pintype "passive"))
      (node (ref "C28") (pin "1") (pinfunction "1_1") (pintype "passive"))
      (node (ref "C30") (pin "-") (pinfunction "-_-") (pintype "passive"))
      (node (ref "C31") (pin "+") (pinfunction "+_+") (pintype "passive"))
      (node (ref "C32") (pin "-") (pinfunction "-_-") (pintype "passive"))
      (node (ref "C33") (pin "+") (pinfunction "+_+") (pintype "passive"))
      (node (ref "C72") (pin "2") (pinfunction "2_2") (pintype "passive"))
      (node (ref "C73") (pin "2") (pinfunction "2_2") (pintype "passive"))
      (node (ref "C84") (pin "-") (pinfunction "-_-") (pintype "passive"))
      (node (ref "C85") (pin "+") (pinfunction "+_+") (pintype "passive"))
      (node (ref "C86") (pin "-") (pinfunction "-_-") (pintype "passive"))
      (node (ref "C87") (pin "+") (pinfunction "+_+") (pintype "passive"))
      (node (ref "C92") (pin "1") (pinfunction "1_1") (pintype "passive"))
      (node (ref "C93") (pin "2") (pinfunction "2_2") (pintype "passive"))
      (node (ref "C94") (pin "2") (pinfunction "2_2") (pintype "passive"))
      (node (ref "C99") (pin "2") (pinfunction "2_2") (pintype "passive"))
      (node (ref "IC4") (pin "4") (pinfunction "GND_4") (pintype "power_in"))
      (node (ref "IC5") (pin "4") (pinfunction "V-_4") (pintype "power_in"))
      (node (ref "IC6") (pin "3") (pinfunction "+IN_3") (pintype "input"))
      (node (ref "IC6") (pin "7") (pinfunction "V+_7") (pintype "power_in"))
      (node (ref "IC7") (pin "4") (pinfunction "GND_4") (pintype "power_in"))
      (node (ref "IC8") (pin "4") (pinfunction "V-_4") (pintype "power_in"))
      (node (ref "IC9") (pin "3") (pinfunction "+IN_3") (pintype "input"))
      (node (ref "IC9") (pin "7") (pinfunction "V+_7") (pintype "power_in"))
      (node (ref "Q1") (pin "C") (pinfunction "C_C") (pintype "passive"))
      (node (ref "Q2") (pin "C") (pinfunction "C_C") (pintype "passive"))
      (node (ref "Q3") (pin "C") (pinfunction "C_C") (pintype "passive"))
      (node (ref "Q4") (pin "C") (pinfunction "C_C") (pintype "passive"))
      (node (ref "R20") (pin "1") (pinfunction "1_1") (pintype "passive"))
      (node (ref "R21") (pin "2") (pinfunction "2_2") (pintype "passive"))
      (node (ref "R23") (pin "1") (pinfunction "1_1") (pintype "passive"))
      (node (ref "R24") (pin "2") (pinfunction "2_2") (pintype "passive"))
      (node (ref "R41") (pin "2") (pinfunction "2_2") (pintype "passive"))
      (node (ref "R49") (pin "1") (pinfunction "1_1") (pintype "passive"))
      (node (ref "R50") (pin "2") (pinfunction "2_2") (pintype "passive"))
      (node (ref "R51") (pin "2") (pinfunction "2_2") (pintype "passive"))
      (node (ref "R52") (pin "2") (pinfunction "2_2") (pintype "passive"))
      (node (ref "R53") (pin "1") (pinfunction "1_1") (pintype "passive"))
      (node (ref "R54") (pin "2") (pinfunction "2_2") (pintype "passive"))
      (node (ref "R73") (pin "1") (pinfunction "1_1") (pintype "passive"))
      (node (ref "R85") (pin "1") (pinfunction "1_1") (pintype "passive"))
      (node (ref "SJ1") (pin "P$2") (pinfunction "2_P$2") (pintype "passive"))
      (node (ref "SJ2") (pin "P$2") (pinfunction "2_P$2") (pintype "passive"))
      (node (ref "U$18") (pin "P$1") (pinfunction "P$1_P$1") (pintype "bidirectional"))
      (node (ref "U$18") (pin "P$2") (pinfunction "P$1_P$2") (pintype "bidirectional"))
      (node (ref "U$18") (pin "P$3") (pinfunction "P$1_P$3") (pintype "bidirectional"))
      (node (ref "U$18") (pin "P$4") (pinfunction "P$1_P$4") (pintype "bidirectional"))
      (node (ref "U$18") (pin "P$5") (pinfunction "P$1_P$5") (pintype "bidirectional"))
      (node (ref "U$18") (pin "P$6") (pinfunction "P$1_P$6") (pintype "bidirectional"))
      (node (ref "U$18") (pin "P$7") (pinfunction "P$1_P$7") (pintype "bidirectional"))
      (node (ref "U$18") (pin "P$8") (pinfunction "P$1_P$8") (pintype "bidirectional"))
      (node (ref "U$19") (pin "P$4") (pinfunction "KL_P$4") (pintype "passive"))
      (node (ref "U$29") (pin "CATHODE") (pinfunction "CATHODE_CATHODE") (pintype "passive"))
      (node (ref "U$30") (pin "ANODE") (pinfunction "ANODE_ANODE") (pintype "passive"))
      (node (ref "U$33") (pin "P$4") (pinfunction "KL_P$4") (pintype "passive"))
      (node (ref "U$37") (pin "CATHODE") (pinfunction "CATHODE_CATHODE") (pintype "passive"))
      (node (ref "U$38") (pin "ANODE") (pinfunction "ANODE_ANODE") (pintype "passive"))
      (node (ref "U$41") (pin "P$4") (pinfunction "KL_P$4") (pintype "passive"))
    )
    (net (code "4") (name "IN+") (class "Default")
      (node (ref "C13") (pin "1") (pinfunction "1_1") (pintype "passive"))
      (node (ref "R45") (pin "1") (pinfunction "1_1") (pintype "passive"))
      (node (ref "R47") (pin "2") (pinfunction "2_2") (pintype "passive"))
      (node (ref "U$1") (pin "1") (pinfunction "G_1") (pintype "passive"))
      (node (ref "U$5") (pin "4") (pinfunction "G_4") (pintype "passive"))
    )
    (net (code "5") (name "IN-") (class "Default")
      (node (ref "C14") (pin "1") (pinfunction "1_1") (pintype "passive"))
      (node (ref "R46") (pin "1") (pinfunction "1_1") (pintype "passive"))
      (node (ref "R48") (pin "2") (pinfunction "2_2") (pintype "passive"))
      (node (ref "U$1") (pin "4") (pinfunction "G_4") (pintype "passive"))
      (node (ref "U$5") (pin "1") (pinfunction "G_1") (pintype "passive"))
    )
    (net (code "6") (name "Net-(C8-Pad1)") (class "Default")
      (node (ref "C8") (pin "1") (pinfunction "1_1") (pintype "passive"))
      (node (ref "CR10") (pin "CATHODE") (pinfunction "CATHODE_CATHODE") (pintype "passive"))
      (node (ref "D9") (pin "C") (pinfunction "C_C") (pintype "passive"))
      (node (ref "R28") (pin "1") (pinfunction "1_1") (pintype "passive"))
      (node (ref "R32") (pin "2") (pinfunction "2_2") (pintype "passive"))
    )
    (net (code "7") (name "Net-(C8-Pad2)") (class "Default")
      (node (ref "C8") (pin "2") (pinfunction "2_2") (pintype "passive"))
      (node (ref "CR9") (pin "ANODE") (pinfunction "ANODE_ANODE") (pintype "passive"))
      (node (ref "D10") (pin "A") (pinfunction "A_A") (pintype "passive"))
      (node (ref "R29") (pin "1") (pinfunction "1_1") (pintype "passive"))
      (node (ref "R33") (pin "2") (pinfunction "2_2") (pintype "passive"))
    )
    (net (code "8") (name "Net-(C9-Pad1)") (class "Default")
      (node (ref "C9") (pin "1") (pinfunction "1_1") (pintype "passive"))
      (node (ref "CR7") (pin "ANODE") (pinfunction "ANODE_ANODE") (pintype "passive"))
      (node (ref "D3") (pin "C") (pinfunction "C_C") (pintype "passive"))
      (node (ref "R22") (pin "2") (pinfunction "2_2") (pintype "passive"))
      (node (ref "R6") (pin "1") (pinfunction "1_1") (pintype "passive"))
    )
    (net (code "9") (name "Net-(C9-Pad2)") (class "Default")
      (node (ref "C9") (pin "2") (pinfunction "2_2") (pintype "passive"))
      (node (ref "CR8") (pin "ANODE") (pinfunction "ANODE_ANODE") (pintype "passive"))
      (node (ref "D4") (pin "A") (pinfunction "A_A") (pintype "passive"))
      (node (ref "R13") (pin "1") (pinfunction "1_1") (pintype "passive"))
      (node (ref "R30") (pin "2") (pinfunction "2_2") (pintype "passive"))
    )
    (net (code "10") (name "Net-(C64-Pad2)") (class "Default")
      (node (ref "C64") (pin "2") (pinfunction "2_2") (pintype "passive"))
      (node (ref "C65") (pin "2") (pinfunction "2_2") (pintype "passive"))
      (node (ref "D22") (pin "A") (pinfunction "A_A") (pintype "passive"))
      (node (ref "R68") (pin "1") (pinfunction "1_1") (pintype "passive"))
    )
    (net (code "11") (name "Net-(C66-Pad1)") (class "Default")
      (node (ref "C66") (pin "1") (pinfunction "1_1") (pintype "passive"))
      (node (ref "C67") (pin "1") (pinfunction "1_1") (pintype "passive"))
      (node (ref "D23") (pin "C") (pinfunction "C_C") (pintype "passive"))
      (node (ref "R70") (pin "2") (pinfunction "2_2") (pintype "passive"))
    )
    (net (code "12") (name "Net-(C88-Pad2)") (class "Default")
      (node (ref "C88") (pin "2") (pinfunction "2_2") (pintype "passive"))
      (node (ref "C89") (pin "2") (pinfunction "2_2") (pintype "passive"))
      (node (ref "D29") (pin "A") (pinfunction "A_A") (pintype "passive"))
      (node (ref "R80") (pin "1") (pinfunction "1_1") (pintype "passive"))
    )
    (net (code "13") (name "Net-(C90-Pad1)") (class "Default")
      (node (ref "C90") (pin "1") (pinfunction "1_1") (pintype "passive"))
      (node (ref "C91") (pin "1") (pinfunction "1_1") (pintype "passive"))
      (node (ref "D30") (pin "C") (pinfunction "C_C") (pintype "passive"))
      (node (ref "R82") (pin "2") (pinfunction "2_2") (pintype "passive"))
    )
    (net (code "14") (name "Net-(IC4-OUT)") (class "Default")
      (node (ref "C73") (pin "1") (pinfunction "1_1") (pintype "passive"))
      (node (ref "C93") (pin "1") (pinfunction "1_1") (pintype "passive"))
      (node (ref "IC4") (pin "6") (pinfunction "OUT_6") (pintype "output"))
      (node (ref "IC5") (pin "3") (pinfunction "+IN_3") (pintype "input"))
    )
    (net (code "15") (name "Net-(IC5--IN)") (class "Default")
      (node (ref "C70") (pin "2") (pinfunction "2_2") (pintype "passive"))
      (node (ref "IC5") (pin "2") (pinfunction "-IN_2") (pintype "input"))
      (node (ref "R73") (pin "2") (pinfunction "2_2") (pintype "passive"))
      (node (ref "R74") (pin "1") (pinfunction "1_1") (pintype "passive"))
    )
    (net (code "16") (name "Net-(IC5-OUT)") (class "Default")
      (node (ref "IC5") (pin "6") (pinfunction "OUT_6") (pintype "output"))
      (node (ref "R72") (pin "1") (pinfunction "1_1") (pintype "passive"))
    )
    (net (code "17") (name "Net-(IC6--IN)") (class "Default")
      (node (ref "C71") (pin "1") (pinfunction "1_1") (pintype "passive"))
      (node (ref "IC6") (pin "2") (pinfunction "-IN_2") (pintype "input"))
      (node (ref "R75") (pin "2") (pinfunction "2_2") (pintype "passive"))
      (node (ref "R76") (pin "1") (pinfunction "1_1") (pintype "passive"))
    )
    (net (code "18") (name "Net-(IC6-OUT)") (class "Default")
      (node (ref "IC6") (pin "6") (pinfunction "OUT_6") (pintype "output"))
      (node (ref "R71") (pin "1") (pinfunction "1_1") (pintype "passive"))
    )
    (net (code "19") (name "Net-(IC7-OUT)") (class "Default")
      (node (ref "C100") (pin "1") (pinfunction "1_1") (pintype "passive"))
      (node (ref "C120") (pin "1") (pinfunction "1_1") (pintype "passive"))
      (node (ref "IC7") (pin "6") (pinfunction "OUT_6") (pintype "output"))
      (node (ref "IC8") (pin "3") (pinfunction "+IN_3") (pintype "input"))
    )
    (net (code "20") (name "Net-(IC8--IN)") (class "Default")
      (node (ref "C97") (pin "2") (pinfunction "2_2") (pintype "passive"))
      (node (ref "IC8") (pin "2") (pinfunction "-IN_2") (pintype "input"))
      (node (ref "R85") (pin "2") (pinfunction "2_2") (pintype "passive"))
      (node (ref "R86") (pin "1") (pinfunction "1_1") (pintype "passive"))
    )
    (net (code "21") (name "Net-(IC8-OUT)") (class "Default")
      (node (ref "IC8") (pin "6") (pinfunction "OUT_6") (pintype "output"))
      (node (ref "R84") (pin "1") (pinfunction "1_1") (pintype "passive"))
    )
    (net (code "22") (name "Net-(IC9--IN)") (class "Default")
      (node (ref "C98") (pin "1") (pinfunction "1_1") (pintype "passive"))
      (node (ref "IC9") (pin "2") (pinfunction "-IN_2") (pintype "input"))
      (node (ref "R87") (pin "2") (pinfunction "2_2") (pintype "passive"))
      (node (ref "R88") (pin "1") (pinfunction "1_1") (pintype "passive"))
    )
    (net (code "23") (name "Net-(IC9-OUT)") (class "Default")
      (node (ref "IC9") (pin "6") (pinfunction "OUT_6") (pintype "output"))
      (node (ref "R83") (pin "1") (pinfunction "1_1") (pintype "passive"))
    )
    (net (code "24") (name "Net-(LED1-PadC)") (class "Default")
      (node (ref "LED1") (pin "C") (pinfunction "C_C") (pintype "passive"))
      (node (ref "R53") (pin "2") (pinfunction "2_2") (pintype "passive"))
    )
    (net (code "25") (name "Net-(LED2-PadA)") (class "Default")
      (node (ref "LED2") (pin "A") (pinfunction "A_A") (pintype "passive"))
      (node (ref "R54") (pin "1") (pinfunction "1_1") (pintype "passive"))
    )
    (net (code "26") (name "Net-(LED3-PadC)") (class "Default")
      (node (ref "LED3") (pin "C") (pinfunction "C_C") (pintype "passive"))
      (node (ref "R49") (pin "2") (pinfunction "2_2") (pintype "passive"))
    )
    (net (code "27") (name "Net-(LED4-PadA)") (class "Default")
      (node (ref "LED4") (pin "A") (pinfunction "A_A") (pintype "passive"))
      (node (ref "R50") (pin "1") (pinfunction "1_1") (pintype "passive"))
    )
    (net (code "28") (name "Net-(LED5-PadC)") (class "Default")
      (node (ref "LED5") (pin "C") (pinfunction "C_C") (pintype "passive"))
      (node (ref "R51") (pin "1") (pinfunction "1_1") (pintype "passive"))
    )
    (net (code "29") (name "Net-(LED6-PadA)") (class "Default")
      (node (ref "LED6") (pin "A") (pinfunction "A_A") (pintype "passive"))
      (node (ref "R52") (pin "1") (pinfunction "1_1") (pintype "passive"))
    )
    (net (code "30") (name "Net-(Q1-PadB)") (class "Default")
      (node (ref "Q1") (pin "B") (pinfunction "B_B") (pintype "passive"))
      (node (ref "R72") (pin "2") (pinfunction "2_2") (pintype "passive"))
    )
    (net (code "31") (name "Net-(Q1-PadE)") (class "Default")
      (node (ref "Q1") (pin "E") (pinfunction "E_E") (pintype "passive"))
      (node (ref "R68") (pin "2") (pinfunction "2_2") (pintype "passive"))
    )
    (net (code "32") (name "Net-(Q2-PadB)") (class "Default")
      (node (ref "Q2") (pin "B") (pinfunction "B_B") (pintype "passive"))
      (node (ref "R71") (pin "2") (pinfunction "2_2") (pintype "passive"))
    )
    (net (code "33") (name "Net-(Q2-PadE)") (class "Default")
      (node (ref "Q2") (pin "E") (pinfunction "E_E") (pintype "passive"))
      (node (ref "R70") (pin "1") (pinfunction "1_1") (pintype "passive"))
    )
    (net (code "34") (name "Net-(Q3-PadB)") (class "Default")
      (node (ref "Q3") (pin "B") (pinfunction "B_B") (pintype "passive"))
      (node (ref "R84") (pin "2") (pinfunction "2_2") (pintype "passive"))
    )
    (net (code "35") (name "Net-(Q3-PadE)") (class "Default")
      (node (ref "Q3") (pin "E") (pinfunction "E_E") (pintype "passive"))
      (node (ref "R80") (pin "2") (pinfunction "2_2") (pintype "passive"))
    )
    (net (code "36") (name "Net-(Q4-PadB)") (class "Default")
      (node (ref "Q4") (pin "B") (pinfunction "B_B") (pintype "passive"))
      (node (ref "R83") (pin "2") (pinfunction "2_2") (pintype "passive"))
    )
    (net (code "37") (name "Net-(Q4-PadE)") (class "Default")
      (node (ref "Q4") (pin "E") (pinfunction "E_E") (pintype "passive"))
      (node (ref "R82") (pin "1") (pinfunction "1_1") (pintype "passive"))
    )
    (net (code "38") (name "Net-(Q21-G)") (class "Default")
      (node (ref "C3") (pin "1") (pinfunction "1_1") (pintype "passive"))
      (node (ref "C7") (pin "1") (pinfunction "1_1") (pintype "passive"))
      (node (ref "Q21") (pin "1") (pinfunction "G_1") (pintype "passive"))
      (node (ref "R23") (pin "2") (pinfunction "2_2") (pintype "passive"))
      (node (ref "R25") (pin "2") (pinfunction "2_2") (pintype "passive"))
      (node (ref "U$12") (pin "6") (pinfunction "C_6") (pintype "passive"))
      (node (ref "U$4") (pin "5") (pinfunction "C1_5") (pintype "passive"))
    )
    (net (code "39") (name "Net-(Q21-S)") (class "Default")
      (node (ref "Q21") (pin "3") (pinfunction "S_3") (pintype "passive"))
      (node (ref "R34") (pin "1") (pinfunction "1_1") (pintype "passive"))
    )
    (net (code "40") (name "Net-(Q22-G)") (class "Default")
      (node (ref "C5") (pin "1") (pinfunction "1_1") (pintype "passive"))
      (node (ref "C7") (pin "2") (pinfunction "2_2") (pintype "passive"))
      (node (ref "Q22") (pin "1") (pinfunction "G_1") (pintype "passive"))
      (node (ref "R24") (pin "1") (pinfunction "1_1") (pintype "passive"))
      (node (ref "R26") (pin "1") (pinfunction "1_1") (pintype "passive"))
      (node (ref "U$4") (pin "4") (pinfunction "C2_4") (pintype "passive"))
      (node (ref "U$8") (pin "6") (pinfunction "C_6") (pintype "passive"))
    )
    (net (code "41") (name "Net-(Q22-S)") (class "Default")
      (node (ref "Q22") (pin "3") (pinfunction "S_3") (pintype "passive"))
      (node (ref "R35") (pin "2") (pinfunction "2_2") (pintype "passive"))
    )
    (net (code "42") (name "Net-(Q23-G)") (class "Default")
      (node (ref "Q23") (pin "1") (pinfunction "G_1") (pintype "passive"))
      (node (ref "R32") (pin "1") (pinfunction "1_1") (pintype "passive"))
    )
    (net (code "43") (name "Net-(Q23-S)") (class "Default")
      (node (ref "Q21") (pin "2") (pinfunction "D_2") (pintype "passive"))
      (node (ref "Q21") (pin "4") (pinfunction "D_4") (pintype "passive"))
      (node (ref "Q21") (pin "P$1") (pinfunction "D_P$1") (pintype "passive"))
      (node (ref "Q21") (pin "P$10") (pinfunction "D_P$10") (pintype "passive"))
      (node (ref "Q21") (pin "P$11") (pinfunction "D_P$11") (pintype "passive"))
      (node (ref "Q21") (pin "P$12") (pinfunction "D_P$12") (pintype "passive"))
      (node (ref "Q21") (pin "P$13") (pinfunction "D_P$13") (pintype "passive"))
      (node (ref "Q21") (pin "P$14") (pinfunction "D_P$14") (pintype "passive"))
      (node (ref "Q21") (pin "P$15") (pinfunction "D_P$15") (pintype "passive"))
      (node (ref "Q21") (pin "P$16") (pinfunction "D_P$16") (pintype "passive"))
      (node (ref "Q21") (pin "P$17") (pinfunction "D_P$17") (pintype "passive"))
      (node (ref "Q21") (pin "P$18") (pinfunction "D_P$18") (pintype "passive"))
      (node (ref "Q21") (pin "P$19") (pinfunction "D_P$19") (pintype "passive"))
      (node (ref "Q21") (pin "P$2") (pinfunction "D_P$2") (pintype "passive"))
      (node (ref "Q21") (pin "P$20") (pinfunction "D_P$20") (pintype "passive"))
      (node (ref "Q21") (pin "P$21") (pinfunction "D_P$21") (pintype "passive"))
      (node (ref "Q21") (pin "P$22") (pinfunction "D_P$22") (pintype "passive"))
      (node (ref "Q21") (pin "P$23") (pinfunction "D_P$23") (pintype "passive"))
      (node (ref "Q21") (pin "P$24") (pinfunction "D_P$24") (pintype "passive"))
      (node (ref "Q21") (pin "P$25") (pinfunction "D_P$25") (pintype "passive"))
      (node (ref "Q21") (pin "P$26") (pinfunction "D_P$26") (pintype "passive"))
      (node (ref "Q21") (pin "P$27") (pinfunction "D_P$27") (pintype "passive"))
      (node (ref "Q21") (pin "P$28") (pinfunction "D_P$28") (pintype "passive"))
      (node (ref "Q21") (pin "P$29") (pinfunction "D_P$29") (pintype "passive"))
      (node (ref "Q21") (pin "P$3") (pinfunction "D_P$3") (pintype "passive"))
      (node (ref "Q21") (pin "P$30") (pinfunction "D_P$30") (pintype "passive"))
      (node (ref "Q21") (pin "P$31") (pinfunction "D_P$31") (pintype "passive"))
      (node (ref "Q21") (pin "P$32") (pinfunction "D_P$32") (pintype "passive"))
      (node (ref "Q21") (pin "P$33") (pinfunction "D_P$33") (pintype "passive"))
      (node (ref "Q21") (pin "P$34") (pinfunction "D_P$34") (pintype "passive"))
      (node (ref "Q21") (pin "P$35") (pinfunction "D_P$35") (pintype "passive"))
      (node (ref "Q21") (pin "P$36") (pinfunction "D_P$36") (pintype "passive"))
      (node (ref "Q21") (pin "P$37") (pinfunction "D_P$37") (pintype "passive"))
      (node (ref "Q21") (pin "P$38") (pinfunction "D_P$38") (pintype "passive"))
      (node (ref "Q21") (pin "P$39") (pinfunction "D_P$39") (pintype "passive"))
      (node (ref "Q21") (pin "P$4") (pinfunction "D_P$4") (pintype "passive"))
      (node (ref "Q21") (pin "P$40") (pinfunction "D_P$40") (pintype "passive"))
      (node (ref "Q21") (pin "P$41") (pinfunction "D_P$41") (pintype "passive"))
      (node (ref "Q21") (pin "P$42") (pinfunction "D_P$42") (pintype "passive"))
      (node (ref "Q21") (pin "P$43") (pinfunction "D_P$43") (pintype "passive"))
      (node (ref "Q21") (pin "P$44") (pinfunction "D_P$44") (pintype "passive"))
      (node (ref "Q21") (pin "P$45") (pinfunction "D_P$45") (pintype "passive"))
      (node (ref "Q21") (pin "P$46") (pinfunction "D_P$46") (pintype "passive"))
      (node (ref "Q21") (pin "P$47") (pinfunction "D_P$47") (pintype "passive"))
      (node (ref "Q21") (pin "P$48") (pinfunction "D_P$48") (pintype "passive"))
      (node (ref "Q21") (pin "P$49") (pinfunction "D_P$49") (pintype "passive"))
      (node (ref "Q21") (pin "P$5") (pinfunction "D_P$5") (pintype "passive"))
      (node (ref "Q21") (pin "P$50") (pinfunction "D_P$50") (pintype "passive"))
      (node (ref "Q21") (pin "P$51") (pinfunction "D_P$51") (pintype "passive"))
      (node (ref "Q21") (pin "P$52") (pinfunction "D_P$52") (pintype "passive"))
      (node (ref "Q21") (pin "P$53") (pinfunction "D_P$53") (pintype "passive"))
      (node (ref "Q21") (pin "P$54") (pinfunction "D_P$54") (pintype "passive"))
      (node (ref "Q21") (pin "P$55") (pinfunction "D_P$55") (pintype "passive"))
      (node (ref "Q21") (pin "P$56") (pinfunction "D_P$56") (pintype "passive"))
      (node (ref "Q21") (pin "P$57") (pinfunction "D_P$57") (pintype "passive"))
      (node (ref "Q21") (pin "P$58") (pinfunction "D_P$58") (pintype "passive"))
      (node (ref "Q21") (pin "P$59") (pinfunction "D_P$59") (pintype "passive"))
      (node (ref "Q21") (pin "P$6") (pinfunction "D_P$6") (pintype "passive"))
      (node (ref "Q21") (pin "P$60") (pinfunction "D_P$60") (pintype "passive"))
      (node (ref "Q21") (pin "P$61") (pinfunction "D_P$61") (pintype "passive"))
      (node (ref "Q21") (pin "P$62") (pinfunction "D_P$62") (pintype "passive"))
      (node (ref "Q21") (pin "P$63") (pinfunction "D_P$63") (pintype "passive"))
      (node (ref "Q21") (pin "P$7") (pinfunction "D_P$7") (pintype "passive"))
      (node (ref "Q21") (pin "P$8") (pinfunction "D_P$8") (pintype "passive"))
      (node (ref "Q21") (pin "P$9") (pinfunction "D_P$9") (pintype "passive"))
      (node (ref "Q23") (pin "3") (pinfunction "S_3") (pintype "passive"))
    )
    (net (code "44") (name "Net-(Q24-G)") (class "Default")
      (node (ref "Q24") (pin "1") (pinfunction "G_1") (pintype "passive"))
      (node (ref "R33") (pin "1") (pinfunction "1_1") (pintype "passive"))
    )
    (net (code "45") (name "Net-(Q24-S)") (class "Default")
      (node (ref "Q22") (pin "2") (pinfunction "D_2") (pintype "passive"))
      (node (ref "Q22") (pin "4") (pinfunction "D_4") (pintype "passive"))
      (node (ref "Q22") (pin "P$1") (pinfunction "D_P$1") (pintype "passive"))
      (node (ref "Q22") (pin "P$10") (pinfunction "D_P$10") (pintype "passive"))
      (node (ref "Q22") (pin "P$11") (pinfunction "D_P$11") (pintype "passive"))
      (node (ref "Q22") (pin "P$12") (pinfunction "D_P$12") (pintype "passive"))
      (node (ref "Q22") (pin "P$13") (pinfunction "D_P$13") (pintype "passive"))
      (node (ref "Q22") (pin "P$14") (pinfunction "D_P$14") (pintype "passive"))
      (node (ref "Q22") (pin "P$15") (pinfunction "D_P$15") (pintype "passive"))
      (node (ref "Q22") (pin "P$16") (pinfunction "D_P$16") (pintype "passive"))
      (node (ref "Q22") (pin "P$17") (pinfunction "D_P$17") (pintype "passive"))
      (node (ref "Q22") (pin "P$18") (pinfunction "D_P$18") (pintype "passive"))
      (node (ref "Q22") (pin "P$19") (pinfunction "D_P$19") (pintype "passive"))
      (node (ref "Q22") (pin "P$2") (pinfunction "D_P$2") (pintype "passive"))
      (node (ref "Q22") (pin "P$20") (pinfunction "D_P$20") (pintype "passive"))
      (node (ref "Q22") (pin "P$21") (pinfunction "D_P$21") (pintype "passive"))
      (node (ref "Q22") (pin "P$22") (pinfunction "D_P$22") (pintype "passive"))
      (node (ref "Q22") (pin "P$23") (pinfunction "D_P$23") (pintype "passive"))
      (node (ref "Q22") (pin "P$24") (pinfunction "D_P$24") (pintype "passive"))
      (node (ref "Q22") (pin "P$25") (pinfunction "D_P$25") (pintype "passive"))
      (node (ref "Q22") (pin "P$26") (pinfunction "D_P$26") (pintype "passive"))
      (node (ref "Q22") (pin "P$27") (pinfunction "D_P$27") (pintype "passive"))
      (node (ref "Q22") (pin "P$28") (pinfunction "D_P$28") (pintype "passive"))
      (node (ref "Q22") (pin "P$29") (pinfunction "D_P$29") (pintype "passive"))
      (node (ref "Q22") (pin "P$3") (pinfunction "D_P$3") (pintype "passive"))
      (node (ref "Q22") (pin "P$30") (pinfunction "D_P$30") (pintype "passive"))
      (node (ref "Q22") (pin "P$31") (pinfunction "D_P$31") (pintype "passive"))
      (node (ref "Q22") (pin "P$32") (pinfunction "D_P$32") (pintype "passive"))
      (node (ref "Q22") (pin "P$33") (pinfunction "D_P$33") (pintype "passive"))
      (node (ref "Q22") (pin "P$34") (pinfunction "D_P$34") (pintype "passive"))
      (node (ref "Q22") (pin "P$35") (pinfunction "D_P$35") (pintype "passive"))
      (node (ref "Q22") (pin "P$36") (pinfunction "D_P$36") (pintype "passive"))
      (node (ref "Q22") (pin "P$37") (pinfunction "D_P$37") (pintype "passive"))
      (node (ref "Q22") (pin "P$38") (pinfunction "D_P$38") (pintype "passive"))
      (node (ref "Q22") (pin "P$39") (pinfunction "D_P$39") (pintype "passive"))
      (node (ref "Q22") (pin "P$4") (pinfunction "D_P$4") (pintype "passive"))
      (node (ref "Q22") (pin "P$40") (pinfunction "D_P$40") (pintype "passive"))
      (node (ref "Q22") (pin "P$41") (pinfunction "D_P$41") (pintype "passive"))
      (node (ref "Q22") (pin "P$42") (pinfunction "D_P$42") (pintype "passive"))
      (node (ref "Q22") (pin "P$43") (pinfunction "D_P$43") (pintype "passive"))
      (node (ref "Q22") (pin "P$44") (pinfunction "D_P$44") (pintype "passive"))
      (node (ref "Q22") (pin "P$45") (pinfunction "D_P$45") (pintype "passive"))
      (node (ref "Q22") (pin "P$46") (pinfunction "D_P$46") (pintype "passive"))
      (node (ref "Q22") (pin "P$47") (pinfunction "D_P$47") (pintype "passive"))
      (node (ref "Q22") (pin "P$48") (pinfunction "D_P$48") (pintype "passive"))
      (node (ref "Q22") (pin "P$49") (pinfunction "D_P$49") (pintype "passive"))
      (node (ref "Q22") (pin "P$5") (pinfunction "D_P$5") (pintype "passive"))
      (node (ref "Q22") (pin "P$50") (pinfunction "D_P$50") (pintype "passive"))
      (node (ref "Q22") (pin "P$51") (pinfunction "D_P$51") (pintype "passive"))
      (node (ref "Q22") (pin "P$52") (pinfunction "D_P$52") (pintype "passive"))
      (node (ref "Q22") (pin "P$53") (pinfunction "D_P$53") (pintype "passive"))
      (node (ref "Q22") (pin "P$54") (pinfunction "D_P$54") (pintype "passive"))
      (node (ref "Q22") (pin "P$55") (pinfunction "D_P$55") (pintype "passive"))
      (node (ref "Q22") (pin "P$56") (pinfunction "D_P$56") (pintype "passive"))
      (node (ref "Q22") (pin "P$57") (pinfunction "D_P$57") (pintype "passive"))
      (node (ref "Q22") (pin "P$58") (pinfunction "D_P$58") (pintype "passive"))
      (node (ref "Q22") (pin "P$59") (pinfunction "D_P$59") (pintype "passive"))
      (node (ref "Q22") (pin "P$6") (pinfunction "D_P$6") (pintype "passive"))
      (node (ref "Q22") (pin "P$60") (pinfunction "D_P$60") (pintype "passive"))
      (node (ref "Q22") (pin "P$61") (pinfunction "D_P$61") (pintype "passive"))
      (node (ref "Q22") (pin "P$62") (pinfunction "D_P$62") (pintype "passive"))
      (node (ref "Q22") (pin "P$63") (pinfunction "D_P$63") (pintype "passive"))
      (node (ref "Q22") (pin "P$7") (pinfunction "D_P$7") (pintype "passive"))
      (node (ref "Q22") (pin "P$8") (pinfunction "D_P$8") (pintype "passive"))
      (node (ref "Q22") (pin "P$9") (pinfunction "D_P$9") (pintype "passive"))
      (node (ref "Q24") (pin "3") (pinfunction "S_3") (pintype "passive"))
    )
    (net (code "46") (name "Net-(Q25-G)") (class "Default")
      (node (ref "C2") (pin "1") (pinfunction "1_1") (pintype "passive"))
      (node (ref "C6") (pin "1") (pinfunction "1_1") (pintype "passive"))
      (node (ref "Q25") (pin "1") (pinfunction "G_1") (pintype "passive"))
      (node (ref "R1") (pin "2") (pinfunction "2_2") (pintype "passive"))
      (node (ref "R20") (pin "2") (pinfunction "2_2") (pintype "passive"))
      (node (ref "U$12") (pin "4") (pinfunction "C_4") (pintype "passive"))
      (node (ref "U$16") (pin "5") (pinfunction "C1_5") (pintype "passive"))
    )
    (net (code "47") (name "Net-(Q25-S)") (class "Default")
      (node (ref "Q25") (pin "3") (pinfunction "S_3") (pintype "passive"))
      (node (ref "R31") (pin "1") (pinfunction "1_1") (pintype "passive"))
    )
    (net (code "48") (name "Net-(Q26-G)") (class "Default")
      (node (ref "C4") (pin "1") (pinfunction "1_1") (pintype "passive"))
      (node (ref "C6") (pin "2") (pinfunction "2_2") (pintype "passive"))
      (node (ref "Q26") (pin "1") (pinfunction "G_1") (pintype "passive"))
      (node (ref "R2") (pin "1") (pinfunction "1_1") (pintype "passive"))
      (node (ref "R21") (pin "1") (pinfunction "1_1") (pintype "passive"))
      (node (ref "U$16") (pin "4") (pinfunction "C2_4") (pintype "passive"))
      (node (ref "U$8") (pin "4") (pinfunction "C_4") (pintype "passive"))
    )
    (net (code "49") (name "Net-(Q26-S)") (class "Default")
      (node (ref "Q26") (pin "3") (pinfunction "S_3") (pintype "passive"))
      (node (ref "R36") (pin "2") (pinfunction "2_2") (pintype "passive"))
    )
    (net (code "50") (name "Net-(Q27-G)") (class "Default")
      (node (ref "Q27") (pin "1") (pinfunction "G_1") (pintype "passive"))
      (node (ref "R22") (pin "1") (pinfunction "1_1") (pintype "passive"))
    )
    (net (code "51") (name "Net-(Q27-S)") (class "Default")
      (node (ref "Q25") (pin "2") (pinfunction "D_2") (pintype "passive"))
      (node (ref "Q25") (pin "4") (pinfunction "D_4") (pintype "passive"))
      (node (ref "Q25") (pin "P$1") (pinfunction "D_P$1") (pintype "passive"))
      (node (ref "Q25") (pin "P$10") (pinfunction "D_P$10") (pintype "passive"))
      (node (ref "Q25") (pin "P$11") (pinfunction "D_P$11") (pintype "passive"))
      (node (ref "Q25") (pin "P$12") (pinfunction "D_P$12") (pintype "passive"))
      (node (ref "Q25") (pin "P$13") (pinfunction "D_P$13") (pintype "passive"))
      (node (ref "Q25") (pin "P$14") (pinfunction "D_P$14") (pintype "passive"))
      (node (ref "Q25") (pin "P$15") (pinfunction "D_P$15") (pintype "passive"))
      (node (ref "Q25") (pin "P$16") (pinfunction "D_P$16") (pintype "passive"))
      (node (ref "Q25") (pin "P$17") (pinfunction "D_P$17") (pintype "passive"))
      (node (ref "Q25") (pin "P$18") (pinfunction "D_P$18") (pintype "passive"))
      (node (ref "Q25") (pin "P$19") (pinfunction "D_P$19") (pintype "passive"))
      (node (ref "Q25") (pin "P$2") (pinfunction "D_P$2") (pintype "passive"))
      (node (ref "Q25") (pin "P$20") (pinfunction "D_P$20") (pintype "passive"))
      (node (ref "Q25") (pin "P$21") (pinfunction "D_P$21") (pintype "passive"))
      (node (ref "Q25") (pin "P$22") (pinfunction "D_P$22") (pintype "passive"))
      (node (ref "Q25") (pin "P$23") (pinfunction "D_P$23") (pintype "passive"))
      (node (ref "Q25") (pin "P$24") (pinfunction "D_P$24") (pintype "passive"))
      (node (ref "Q25") (pin "P$25") (pinfunction "D_P$25") (pintype "passive"))
      (node (ref "Q25") (pin "P$26") (pinfunction "D_P$26") (pintype "passive"))
      (node (ref "Q25") (pin "P$27") (pinfunction "D_P$27") (pintype "passive"))
      (node (ref "Q25") (pin "P$28") (pinfunction "D_P$28") (pintype "passive"))
      (node (ref "Q25") (pin "P$29") (pinfunction "D_P$29") (pintype "passive"))
      (node (ref "Q25") (pin "P$3") (pinfunction "D_P$3") (pintype "passive"))
      (node (ref "Q25") (pin "P$30") (pinfunction "D_P$30") (pintype "passive"))
      (node (ref "Q25") (pin "P$31") (pinfunction "D_P$31") (pintype "passive"))
      (node (ref "Q25") (pin "P$32") (pinfunction "D_P$32") (pintype "passive"))
      (node (ref "Q25") (pin "P$33") (pinfunction "D_P$33") (pintype "passive"))
      (node (ref "Q25") (pin "P$34") (pinfunction "D_P$34") (pintype "passive"))
      (node (ref "Q25") (pin "P$35") (pinfunction "D_P$35") (pintype "passive"))
      (node (ref "Q25") (pin "P$36") (pinfunction "D_P$36") (pintype "passive"))
      (node (ref "Q25") (pin "P$37") (pinfunction "D_P$37") (pintype "passive"))
      (node (ref "Q25") (pin "P$38") (pinfunction "D_P$38") (pintype "passive"))
      (node (ref "Q25") (pin "P$39") (pinfunction "D_P$39") (pintype "passive"))
      (node (ref "Q25") (pin "P$4") (pinfunction "D_P$4") (pintype "passive"))
      (node (ref "Q25") (pin "P$40") (pinfunction "D_P$40") (pintype "passive"))
      (node (ref "Q25") (pin "P$41") (pinfunction "D_P$41") (pintype "passive"))
      (node (ref "Q25") (pin "P$42") (pinfunction "D_P$42") (pintype "passive"))
      (node (ref "Q25") (pin "P$43") (pinfunction "D_P$43") (pintype "passive"))
      (node (ref "Q25") (pin "P$44") (pinfunction "D_P$44") (pintype "passive"))
      (node (ref "Q25") (pin "P$45") (pinfunction "D_P$45") (pintype "passive"))
      (node (ref "Q25") (pin "P$46") (pinfunction "D_P$46") (pintype "passive"))
      (node (ref "Q25") (pin "P$47") (pinfunction "D_P$47") (pintype "passive"))
      (node (ref "Q25") (pin "P$48") (pinfunction "D_P$48") (pintype "passive"))
      (node (ref "Q25") (pin "P$49") (pinfunction "D_P$49") (pintype "passive"))
      (node (ref "Q25") (pin "P$5") (pinfunction "D_P$5") (pintype "passive"))
      (node (ref "Q25") (pin "P$50") (pinfunction "D_P$50") (pintype "passive"))
      (node (ref "Q25") (pin "P$51") (pinfunction "D_P$51") (pintype "passive"))
      (node (ref "Q25") (pin "P$52") (pinfunction "D_P$52") (pintype "passive"))
      (node (ref "Q25") (pin "P$53") (pinfunction "D_P$53") (pintype "passive"))
      (node (ref "Q25") (pin "P$54") (pinfunction "D_P$54") (pintype "passive"))
      (node (ref "Q25") (pin "P$55") (pinfunction "D_P$55") (pintype "passive"))
      (node (ref "Q25") (pin "P$56") (pinfunction "D_P$56") (pintype "passive"))
      (node (ref "Q25") (pin "P$57") (pinfunction "D_P$57") (pintype "passive"))
      (node (ref "Q25") (pin "P$58") (pinfunction "D_P$58") (pintype "passive"))
      (node (ref "Q25") (pin "P$59") (pinfunction "D_P$59") (pintype "passive"))
      (node (ref "Q25") (pin "P$6") (pinfunction "D_P$6") (pintype "passive"))
      (node (ref "Q25") (pin "P$60") (pinfunction "D_P$60") (pintype "passive"))
      (node (ref "Q25") (pin "P$61") (pinfunction "D_P$61") (pintype "passive"))
      (node (ref "Q25") (pin "P$62") (pinfunction "D_P$62") (pintype "passive"))
      (node (ref "Q25") (pin "P$63") (pinfunction "D_P$63") (pintype "passive"))
      (node (ref "Q25") (pin "P$7") (pinfunction "D_P$7") (pintype "passive"))
      (node (ref "Q25") (pin "P$8") (pinfunction "D_P$8") (pintype "passive"))
      (node (ref "Q25") (pin "P$9") (pinfunction "D_P$9") (pintype "passive"))
      (node (ref "Q27") (pin "3") (pinfunction "S_3") (pintype "passive"))
    )
    (net (code "52") (name "Net-(Q28-G)") (class "Default")
      (node (ref "Q28") (pin "1") (pinfunction "G_1") (pintype "passive"))
      (node (ref "R30") (pin "1") (pinfunction "1_1") (pintype "passive"))
    )
    (net (code "53") (name "Net-(Q28-S)") (class "Default")
      (node (ref "Q26") (pin "2") (pinfunction "D_2") (pintype "passive"))
      (node (ref "Q26") (pin "4") (pinfunction "D_4") (pintype "passive"))
      (node (ref "Q26") (pin "P$1") (pinfunction "D_P$1") (pintype "passive"))
      (node (ref "Q26") (pin "P$10") (pinfunction "D_P$10") (pintype "passive"))
      (node (ref "Q26") (pin "P$11") (pinfunction "D_P$11") (pintype "passive"))
      (node (ref "Q26") (pin "P$12") (pinfunction "D_P$12") (pintype "passive"))
      (node (ref "Q26") (pin "P$13") (pinfunction "D_P$13") (pintype "passive"))
      (node (ref "Q26") (pin "P$14") (pinfunction "D_P$14") (pintype "passive"))
      (node (ref "Q26") (pin "P$15") (pinfunction "D_P$15") (pintype "passive"))
      (node (ref "Q26") (pin "P$16") (pinfunction "D_P$16") (pintype "passive"))
      (node (ref "Q26") (pin "P$17") (pinfunction "D_P$17") (pintype "passive"))
      (node (ref "Q26") (pin "P$18") (pinfunction "D_P$18") (pintype "passive"))
      (node (ref "Q26") (pin "P$19") (pinfunction "D_P$19") (pintype "passive"))
      (node (ref "Q26") (pin "P$2") (pinfunction "D_P$2") (pintype "passive"))
      (node (ref "Q26") (pin "P$20") (pinfunction "D_P$20") (pintype "passive"))
      (node (ref "Q26") (pin "P$21") (pinfunction "D_P$21") (pintype "passive"))
      (node (ref "Q26") (pin "P$22") (pinfunction "D_P$22") (pintype "passive"))
      (node (ref "Q26") (pin "P$23") (pinfunction "D_P$23") (pintype "passive"))
      (node (ref "Q26") (pin "P$24") (pinfunction "D_P$24") (pintype "passive"))
      (node (ref "Q26") (pin "P$25") (pinfunction "D_P$25") (pintype "passive"))
      (node (ref "Q26") (pin "P$26") (pinfunction "D_P$26") (pintype "passive"))
      (node (ref "Q26") (pin "P$27") (pinfunction "D_P$27") (pintype "passive"))
      (node (ref "Q26") (pin "P$28") (pinfunction "D_P$28") (pintype "passive"))
      (node (ref "Q26") (pin "P$29") (pinfunction "D_P$29") (pintype "passive"))
      (node (ref "Q26") (pin "P$3") (pinfunction "D_P$3") (pintype "passive"))
      (node (ref "Q26") (pin "P$30") (pinfunction "D_P$30") (pintype "passive"))
      (node (ref "Q26") (pin "P$31") (pinfunction "D_P$31") (pintype "passive"))
      (node (ref "Q26") (pin "P$32") (pinfunction "D_P$32") (pintype "passive"))
      (node (ref "Q26") (pin "P$33") (pinfunction "D_P$33") (pintype "passive"))
      (node (ref "Q26") (pin "P$34") (pinfunction "D_P$34") (pintype "passive"))
      (node (ref "Q26") (pin "P$35") (pinfunction "D_P$35") (pintype "passive"))
      (node (ref "Q26") (pin "P$36") (pinfunction "D_P$36") (pintype "passive"))
      (node (ref "Q26") (pin "P$37") (pinfunction "D_P$37") (pintype "passive"))
      (node (ref "Q26") (pin "P$38") (pinfunction "D_P$38") (pintype "passive"))
      (node (ref "Q26") (pin "P$39") (pinfunction "D_P$39") (pintype "passive"))
      (node (ref "Q26") (pin "P$4") (pinfunction "D_P$4") (pintype "passive"))
      (node (ref "Q26") (pin "P$40") (pinfunction "D_P$40") (pintype "passive"))
      (node (ref "Q26") (pin "P$41") (pinfunction "D_P$41") (pintype "passive"))
      (node (ref "Q26") (pin "P$42") (pinfunction "D_P$42") (pintype "passive"))
      (node (ref "Q26") (pin "P$43") (pinfunction "D_P$43") (pintype "passive"))
      (node (ref "Q26") (pin "P$44") (pinfunction "D_P$44") (pintype "passive"))
      (node (ref "Q26") (pin "P$45") (pinfunction "D_P$45") (pintype "passive"))
      (node (ref "Q26") (pin "P$46") (pinfunction "D_P$46") (pintype "passive"))
      (node (ref "Q26") (pin "P$47") (pinfunction "D_P$47") (pintype "passive"))
      (node (ref "Q26") (pin "P$48") (pinfunction "D_P$48") (pintype "passive"))
      (node (ref "Q26") (pin "P$49") (pinfunction "D_P$49") (pintype "passive"))
      (node (ref "Q26") (pin "P$5") (pinfunction "D_P$5") (pintype "passive"))
      (node (ref "Q26") (pin "P$50") (pinfunction "D_P$50") (pintype "passive"))
      (node (ref "Q26") (pin "P$51") (pinfunction "D_P$51") (pintype "passive"))
      (node (ref "Q26") (pin "P$52") (pinfunction "D_P$52") (pintype "passive"))
      (node (ref "Q26") (pin "P$53") (pinfunction "D_P$53") (pintype "passive"))
      (node (ref "Q26") (pin "P$54") (pinfunction "D_P$54") (pintype "passive"))
      (node (ref "Q26") (pin "P$55") (pinfunction "D_P$55") (pintype "passive"))
      (node (ref "Q26") (pin "P$56") (pinfunction "D_P$56") (pintype "passive"))
      (node (ref "Q26") (pin "P$57") (pinfunction "D_P$57") (pintype "passive"))
      (node (ref "Q26") (pin "P$58") (pinfunction "D_P$58") (pintype "passive"))
      (node (ref "Q26") (pin "P$59") (pinfunction "D_P$59") (pintype "passive"))
      (node (ref "Q26") (pin "P$6") (pinfunction "D_P$6") (pintype "passive"))
      (node (ref "Q26") (pin "P$60") (pinfunction "D_P$60") (pintype "passive"))
      (node (ref "Q26") (pin "P$61") (pinfunction "D_P$61") (pintype "passive"))
      (node (ref "Q26") (pin "P$62") (pinfunction "D_P$62") (pintype "passive"))
      (node (ref "Q26") (pin "P$63") (pinfunction "D_P$63") (pintype "passive"))
      (node (ref "Q26") (pin "P$7") (pinfunction "D_P$7") (pintype "passive"))
      (node (ref "Q26") (pin "P$8") (pinfunction "D_P$8") (pintype "passive"))
      (node (ref "Q26") (pin "P$9") (pinfunction "D_P$9") (pintype "passive"))
      (node (ref "Q28") (pin "3") (pinfunction "S_3") (pintype "passive"))
    )
    (net (code "54") (name "Net-(SJ1-1)") (class "Default")
      (node (ref "R45") (pin "2") (pinfunction "2_2") (pintype "passive"))
      (node (ref "SJ1") (pin "P$1") (pinfunction "1_P$1") (pintype "passive"))
    )
    (net (code "55") (name "Net-(SJ2-1)") (class "Default")
      (node (ref "R46") (pin "2") (pinfunction "2_2") (pintype "passive"))
      (node (ref "SJ2") (pin "P$1") (pinfunction "1_P$1") (pintype "passive"))
    )
    (net (code "56") (name "Net-(U$1A-D)") (class "Default")
      (node (ref "U$1") (pin "2") (pinfunction "D_2") (pintype "passive"))
      (node (ref "U$2") (pin "5") (pinfunction "E_5") (pintype "passive"))
    )
    (net (code "57") (name "Net-(U$1A-S)") (class "Default")
      (node (ref "U$1") (pin "3") (pinfunction "S_3") (pintype "passive"))
      (node (ref "VR4") (pin "3") (pinfunction "E_3") (pintype "passive"))
    )
    (net (code "58") (name "Net-(U$1B-D)") (class "Default")
      (node (ref "U$1") (pin "5") (pinfunction "D_5") (pintype "passive"))
      (node (ref "U$2") (pin "2") (pinfunction "E_2") (pintype "passive"))
    )
    (net (code "59") (name "Net-(U$1B-S)") (class "Default")
      (node (ref "U$1") (pin "6") (pinfunction "S_6") (pintype "passive"))
      (node (ref "VR4") (pin "1") (pinfunction "A_1") (pintype "passive"))
    )
    (net (code "60") (name "Net-(U$2A-B)") (class "Default")
      (node (ref "CR1") (pin "CATHODE") (pinfunction "CATHODE_CATHODE") (pintype "passive"))
      (node (ref "D1") (pin "C") (pinfunction "C_C") (pintype "passive"))
      (node (ref "U$2") (pin "1") (pinfunction "B_1") (pintype "passive"))
      (node (ref "U$2") (pin "3") (pinfunction "B_3") (pintype "passive"))
    )
    (net (code "61") (name "Net-(U$3A-D)") (class "Default")
      (node (ref "U$3") (pin "2") (pinfunction "D_2") (pintype "passive"))
      (node (ref "U$6") (pin "5") (pinfunction "E_5") (pintype "passive"))
    )
    (net (code "62") (name "Net-(U$3A-S)") (class "Default")
      (node (ref "D11") (pin "A") (pinfunction "A_A") (pintype "passive"))
      (node (ref "R43") (pin "1") (pinfunction "1_1") (pintype "passive"))
      (node (ref "U$3") (pin "3") (pinfunction "S_3") (pintype "passive"))
      (node (ref "U$3") (pin "6") (pinfunction "S_6") (pintype "passive"))
    )
    (net (code "63") (name "Net-(U$3B-D)") (class "Default")
      (node (ref "U$3") (pin "5") (pinfunction "D_5") (pintype "passive"))
      (node (ref "U$6") (pin "2") (pinfunction "E_2") (pintype "passive"))
    )
    (net (code "64") (name "Net-(U$4-B1)") (class "Default")
      (node (ref "R25") (pin "1") (pinfunction "1_1") (pintype "passive"))
      (node (ref "U$4") (pin "1") (pinfunction "B1_1") (pintype "passive"))
      (node (ref "VR3") (pin "1") (pinfunction "A_1") (pintype "passive"))
      (node (ref "VR3") (pin "2") (pinfunction "S_2") (pintype "passive"))
    )
    (net (code "65") (name "Net-(U$4-B2)") (class "Default")
      (node (ref "R26") (pin "2") (pinfunction "2_2") (pintype "passive"))
      (node (ref "R27") (pin "1") (pinfunction "1_1") (pintype "passive"))
      (node (ref "U$4") (pin "3") (pinfunction "B2_3") (pintype "passive"))
    )
    (net (code "66") (name "Net-(U$5A-S)") (class "Default")
      (node (ref "R8") (pin "1") (pinfunction "1_1") (pintype "passive"))
      (node (ref "U$5") (pin "3") (pinfunction "S_3") (pintype "passive"))
    )
    (net (code "67") (name "Net-(U$5B-S)") (class "Default")
      (node (ref "R7") (pin "2") (pinfunction "2_2") (pintype "passive"))
      (node (ref "U$5") (pin "6") (pinfunction "S_6") (pintype "passive"))
    )
    (net (code "68") (name "Net-(U$6A-B)") (class "Default")
      (node (ref "CR3") (pin "CATHODE") (pinfunction "CATHODE_CATHODE") (pintype "passive"))
      (node (ref "D11") (pin "C") (pinfunction "C_C") (pintype "passive"))
      (node (ref "U$6") (pin "1") (pinfunction "B_1") (pintype "passive"))
      (node (ref "U$6") (pin "3") (pinfunction "B_3") (pintype "passive"))
    )
    (net (code "69") (name "Net-(U$6A-C)") (class "Default")
      (node (ref "C1") (pin "2") (pinfunction "2_2") (pintype "passive"))
      (node (ref "R37") (pin "2") (pinfunction "2_2") (pintype "passive"))
      (node (ref "U$6") (pin "6") (pinfunction "C_6") (pintype "passive"))
    )
    (net (code "70") (name "Net-(U$7A-C)") (class "Default")
      (node (ref "U$7") (pin "6") (pinfunction "C_6") (pintype "passive"))
      (node (ref "U$8") (pin "5") (pinfunction "E_5") (pintype "passive"))
    )
    (net (code "71") (name "Net-(U$7A-E)") (class "Default")
      (node (ref "R19") (pin "2") (pinfunction "2_2") (pintype "passive"))
      (node (ref "U$7") (pin "5") (pinfunction "E_5") (pintype "passive"))
    )
    (net (code "72") (name "Net-(U$7B-C)") (class "Default")
      (node (ref "U$7") (pin "4") (pinfunction "C_4") (pintype "passive"))
      (node (ref "U$8") (pin "2") (pinfunction "E_2") (pintype "passive"))
    )
    (net (code "73") (name "Net-(U$7B-E)") (class "Default")
      (node (ref "R18") (pin "1") (pinfunction "1_1") (pintype "passive"))
      (node (ref "U$7") (pin "2") (pinfunction "E_2") (pintype "passive"))
    )
    (net (code "74") (name "Net-(U$8A-B)") (class "Default")
      (node (ref "CR6") (pin "CATHODE") (pinfunction "CATHODE_CATHODE") (pintype "passive"))
      (node (ref "D8") (pin "C") (pinfunction "C_C") (pintype "passive"))
      (node (ref "U$8") (pin "1") (pinfunction "B_1") (pintype "passive"))
    )
    (net (code "75") (name "Net-(U$8B-B)") (class "Default")
      (node (ref "CR5") (pin "CATHODE") (pinfunction "CATHODE_CATHODE") (pintype "passive"))
      (node (ref "D7") (pin "C") (pinfunction "C_C") (pintype "passive"))
      (node (ref "U$8") (pin "3") (pinfunction "B_3") (pintype "passive"))
    )
    (net (code "76") (name "Net-(U$9A-B)") (class "Default")
      (node (ref "CR4") (pin "ANODE") (pinfunction "ANODE_ANODE") (pintype "passive"))
      (node (ref "D12") (pin "A") (pinfunction "A_A") (pintype "passive"))
      (node (ref "U$9") (pin "1") (pinfunction "B_1") (pintype "passive"))
      (node (ref "U$9") (pin "3") (pinfunction "B_3") (pintype "passive"))
    )
    (net (code "77") (name "Net-(U$9B-C)") (class "Default")
      (node (ref "C11") (pin "1") (pinfunction "1_1") (pintype "passive"))
      (node (ref "R39") (pin "1") (pinfunction "1_1") (pintype "passive"))
      (node (ref "U$9") (pin "4") (pinfunction "C_4") (pintype "passive"))
    )
    (net (code "78") (name "Net-(U$10A-B)") (class "Default")
      (node (ref "CR2") (pin "ANODE") (pinfunction "ANODE_ANODE") (pintype "passive"))
      (node (ref "D2") (pin "A") (pinfunction "A_A") (pintype "passive"))
      (node (ref "U$10") (pin "1") (pinfunction "B_1") (pintype "passive"))
      (node (ref "U$10") (pin "3") (pinfunction "B_3") (pintype "passive"))
    )
    (net (code "79") (name "Net-(U$10A-C)") (class "Default")
      (node (ref "C5") (pin "2") (pinfunction "2_2") (pintype "passive"))
      (node (ref "R12") (pin "1") (pinfunction "1_1") (pintype "passive"))
      (node (ref "U$10") (pin "6") (pinfunction "C_6") (pintype "passive"))
      (node (ref "U$7") (pin "1") (pinfunction "B_1") (pintype "passive"))
    )
    (net (code "80") (name "Net-(U$10A-E)") (class "Default")
      (node (ref "U$10") (pin "5") (pinfunction "E_5") (pintype "passive"))
      (node (ref "U$5") (pin "2") (pinfunction "D_2") (pintype "passive"))
    )
    (net (code "81") (name "Net-(U$10B-C)") (class "Default")
      (node (ref "C4") (pin "2") (pinfunction "2_2") (pintype "passive"))
      (node (ref "R11") (pin "1") (pinfunction "1_1") (pintype "passive"))
      (node (ref "U$10") (pin "4") (pinfunction "C_4") (pintype "passive"))
      (node (ref "U$7") (pin "3") (pinfunction "B_3") (pintype "passive"))
    )
    (net (code "82") (name "Net-(U$10B-E)") (class "Default")
      (node (ref "U$10") (pin "2") (pinfunction "E_2") (pintype "passive"))
      (node (ref "U$5") (pin "5") (pinfunction "D_5") (pintype "passive"))
    )
    (net (code "83") (name "Net-(U$11A-B)") (class "Default")
      (node (ref "C3") (pin "2") (pinfunction "2_2") (pintype "passive"))
      (node (ref "R10") (pin "2") (pinfunction "2_2") (pintype "passive"))
      (node (ref "U$11") (pin "1") (pinfunction "B_1") (pintype "passive"))
      (node (ref "U$2") (pin "4") (pinfunction "C_4") (pintype "passive"))
    )
    (net (code "84") (name "Net-(U$11A-C)") (class "Default")
      (node (ref "U$11") (pin "6") (pinfunction "C_6") (pintype "passive"))
      (node (ref "U$12") (pin "5") (pinfunction "E_5") (pintype "passive"))
    )
    (net (code "85") (name "Net-(U$11A-E)") (class "Default")
      (node (ref "R17") (pin "2") (pinfunction "2_2") (pintype "passive"))
      (node (ref "U$11") (pin "5") (pinfunction "E_5") (pintype "passive"))
    )
    (net (code "86") (name "Net-(U$11B-B)") (class "Default")
      (node (ref "C2") (pin "2") (pinfunction "2_2") (pintype "passive"))
      (node (ref "R9") (pin "2") (pinfunction "2_2") (pintype "passive"))
      (node (ref "U$11") (pin "3") (pinfunction "B_3") (pintype "passive"))
      (node (ref "U$2") (pin "6") (pinfunction "C_6") (pintype "passive"))
    )
    (net (code "87") (name "Net-(U$11B-C)") (class "Default")
      (node (ref "U$11") (pin "4") (pinfunction "C_4") (pintype "passive"))
      (node (ref "U$12") (pin "2") (pinfunction "E_2") (pintype "passive"))
    )
    (net (code "88") (name "Net-(U$11B-E)") (class "Default")
      (node (ref "R16") (pin "1") (pinfunction "1_1") (pintype "passive"))
      (node (ref "U$11") (pin "2") (pinfunction "E_2") (pintype "passive"))
    )
    (net (code "89") (name "Net-(U$12A-B)") (class "Default")
      (node (ref "CR6") (pin "ANODE") (pinfunction "ANODE_ANODE") (pintype "passive"))
      (node (ref "D6") (pin "A") (pinfunction "A_A") (pintype "passive"))
      (node (ref "U$12") (pin "1") (pinfunction "B_1") (pintype "passive"))
    )
    (net (code "90") (name "Net-(U$12B-B)") (class "Default")
      (node (ref "CR5") (pin "ANODE") (pinfunction "ANODE_ANODE") (pintype "passive"))
      (node (ref "D5") (pin "A") (pinfunction "A_A") (pintype "passive"))
      (node (ref "U$12") (pin "3") (pinfunction "B_3") (pintype "passive"))
    )
    (net (code "91") (name "Net-(U$13A-B)") (class "Default")
      (node (ref "C12") (pin "1") (pinfunction "1_1") (pintype "passive"))
      (node (ref "U$13") (pin "1") (pinfunction "B_1") (pintype "passive"))
      (node (ref "U$13") (pin "3") (pinfunction "B_3") (pintype "passive"))
      (node (ref "U$13") (pin "4") (pinfunction "C_4") (pintype "passive"))
      (node (ref "U$9") (pin "6") (pinfunction "C_6") (pintype "passive"))
    )
    (net (code "92") (name "Net-(U$13A-E)") (class "Default")
      (node (ref "R44") (pin "1") (pinfunction "1_1") (pintype "passive"))
      (node (ref "U$13") (pin "5") (pinfunction "E_5") (pintype "passive"))
    )
    (net (code "93") (name "Net-(U$13B-E)") (class "Default")
      (node (ref "R40") (pin "1") (pinfunction "1_1") (pintype "passive"))
      (node (ref "U$13") (pin "2") (pinfunction "E_2") (pintype "passive"))
    )
    (net (code "94") (name "Net-(U$14A-B)") (class "Default")
      (node (ref "C10") (pin "2") (pinfunction "2_2") (pintype "passive"))
      (node (ref "U$14") (pin "1") (pinfunction "B_1") (pintype "passive"))
      (node (ref "U$14") (pin "3") (pinfunction "B_3") (pintype "passive"))
      (node (ref "U$14") (pin "4") (pinfunction "C_4") (pintype "passive"))
      (node (ref "U$6") (pin "4") (pinfunction "C_4") (pintype "passive"))
    )
    (net (code "95") (name "Net-(U$14A-E)") (class "Default")
      (node (ref "R42") (pin "2") (pinfunction "2_2") (pintype "passive"))
      (node (ref "U$14") (pin "5") (pinfunction "E_5") (pintype "passive"))
    )
    (net (code "96") (name "Net-(U$14B-E)") (class "Default")
      (node (ref "R38") (pin "2") (pinfunction "2_2") (pintype "passive"))
      (node (ref "U$14") (pin "2") (pinfunction "E_2") (pintype "passive"))
    )
    (net (code "97") (name "Net-(U$15A-D)") (class "Default")
      (node (ref "U$15") (pin "2") (pinfunction "D_2") (pintype "passive"))
      (node (ref "U$9") (pin "5") (pinfunction "E_5") (pintype "passive"))
    )
    (net (code "98") (name "Net-(U$15A-G)") (class "Default")
      (node (ref "C10") (pin "1") (pinfunction "1_1") (pintype "passive"))
      (node (ref "C12") (pin "2") (pinfunction "2_2") (pintype "passive"))
      (node (ref "R41") (pin "1") (pinfunction "1_1") (pintype "passive"))
      (node (ref "U$15") (pin "1") (pinfunction "G_1") (pintype "passive"))
      (node (ref "U$3") (pin "4") (pinfunction "G_4") (pintype "passive"))
    )
    (net (code "99") (name "Net-(U$15A-S)") (class "Default")
      (node (ref "D12") (pin "C") (pinfunction "C_C") (pintype "passive"))
      (node (ref "R43") (pin "2") (pinfunction "2_2") (pintype "passive"))
      (node (ref "U$15") (pin "3") (pinfunction "S_3") (pintype "passive"))
      (node (ref "U$15") (pin "6") (pinfunction "S_6") (pintype "passive"))
    )
    (net (code "100") (name "Net-(U$15B-D)") (class "Default")
      (node (ref "U$15") (pin "5") (pinfunction "D_5") (pintype "passive"))
      (node (ref "U$9") (pin "2") (pinfunction "E_2") (pintype "passive"))
    )
    (net (code "101") (name "Net-(U$15B-G)") (class "Default")
      (node (ref "C1") (pin "1") (pinfunction "1_1") (pintype "passive"))
      (node (ref "C11") (pin "2") (pinfunction "2_2") (pintype "passive"))
      (node (ref "R3") (pin "2") (pinfunction "2_2") (pintype "passive"))
      (node (ref "R4") (pin "1") (pinfunction "1_1") (pintype "passive"))
      (node (ref "U$15") (pin "4") (pinfunction "G_4") (pintype "passive"))
      (node (ref "U$3") (pin "1") (pinfunction "G_1") (pintype "passive"))
    )
    (net (code "102") (name "Net-(U$16-B1)") (class "Default")
      (node (ref "R1") (pin "1") (pinfunction "1_1") (pintype "passive"))
      (node (ref "U$16") (pin "1") (pinfunction "B1_1") (pintype "passive"))
      (node (ref "VR2") (pin "1") (pinfunction "A_1") (pintype "passive"))
      (node (ref "VR2") (pin "2") (pinfunction "S_2") (pintype "passive"))
    )
    (net (code "103") (name "Net-(U$16-B2)") (class "Default")
      (node (ref "R2") (pin "2") (pinfunction "2_2") (pintype "passive"))
      (node (ref "R5") (pin "1") (pinfunction "1_1") (pintype "passive"))
      (node (ref "U$16") (pin "3") (pinfunction "B2_3") (pintype "passive"))
    )
    (net (code "104") (name "Net-(U$27-B)") (class "Default")
      (node (ref "C64") (pin "1") (pinfunction "1_1") (pintype "passive"))
      (node (ref "C65") (pin "1") (pinfunction "1_1") (pintype "passive"))
      (node (ref "D22") (pin "C") (pinfunction "C_C") (pintype "passive"))
      (node (ref "U$27") (pin "1") (pinfunction "B_1") (pintype "passive"))
      (node (ref "U$32") (pin "4") (pinfunction "C2_4") (pintype "passive"))
    )
    (net (code "105") (name "Net-(U$28-B)") (class "Default")
      (node (ref "C66") (pin "2") (pinfunction "2_2") (pintype "passive"))
      (node (ref "C67") (pin "2") (pinfunction "2_2") (pintype "passive"))
      (node (ref "D23") (pin "A") (pinfunction "A_A") (pintype "passive"))
      (node (ref "U$28") (pin "1") (pinfunction "B_1") (pintype "passive"))
      (node (ref "U$31") (pin "4") (pinfunction "C2_4") (pintype "passive"))
    )
    (net (code "106") (name "Net-(U$31-B)") (class "Default")
      (node (ref "U$30") (pin "CATHODE") (pinfunction "CATHODE_CATHODE") (pintype "passive"))
      (node (ref "U$31") (pin "2") (pinfunction "B_2") (pintype "passive"))
      (node (ref "U$31") (pin "5") (pinfunction "C1_5") (pintype "passive"))
    )
    (net (code "107") (name "Net-(U$31-E1)") (class "Default")
      (node (ref "D21") (pin "A") (pinfunction "A_A") (pintype "passive"))
      (node (ref "U$31") (pin "1") (pinfunction "E1_1") (pintype "passive"))
    )
    (net (code "108") (name "Net-(U$31-E2)") (class "Default")
      (node (ref "R69") (pin "1") (pinfunction "1_1") (pintype "passive"))
      (node (ref "U$31") (pin "3") (pinfunction "E2_3") (pintype "passive"))
    )
    (net (code "109") (name "Net-(U$32-B)") (class "Default")
      (node (ref "U$29") (pin "ANODE") (pinfunction "ANODE_ANODE") (pintype "passive"))
      (node (ref "U$32") (pin "2") (pinfunction "B_2") (pintype "passive"))
      (node (ref "U$32") (pin "5") (pinfunction "C1_5") (pintype "passive"))
    )
    (net (code "110") (name "Net-(U$32-E1)") (class "Default")
      (node (ref "D20") (pin "C") (pinfunction "C_C") (pintype "passive"))
      (node (ref "U$32") (pin "1") (pinfunction "E1_1") (pintype "passive"))
    )
    (net (code "111") (name "Net-(U$32-E2)") (class "Default")
      (node (ref "R67") (pin "2") (pinfunction "2_2") (pintype "passive"))
      (node (ref "U$32") (pin "3") (pinfunction "E2_3") (pintype "passive"))
    )
    (net (code "112") (name "Net-(U$35-B)") (class "Default")
      (node (ref "C88") (pin "1") (pinfunction "1_1") (pintype "passive"))
      (node (ref "C89") (pin "1") (pinfunction "1_1") (pintype "passive"))
      (node (ref "D29") (pin "C") (pinfunction "C_C") (pintype "passive"))
      (node (ref "U$35") (pin "1") (pinfunction "B_1") (pintype "passive"))
      (node (ref "U$40") (pin "4") (pinfunction "C2_4") (pintype "passive"))
    )
    (net (code "113") (name "Net-(U$36-B)") (class "Default")
      (node (ref "C90") (pin "2") (pinfunction "2_2") (pintype "passive"))
      (node (ref "C91") (pin "2") (pinfunction "2_2") (pintype "passive"))
      (node (ref "D30") (pin "A") (pinfunction "A_A") (pintype "passive"))
      (node (ref "U$36") (pin "1") (pinfunction "B_1") (pintype "passive"))
      (node (ref "U$39") (pin "4") (pinfunction "C2_4") (pintype "passive"))
    )
    (net (code "114") (name "Net-(U$39-B)") (class "Default")
      (node (ref "U$38") (pin "CATHODE") (pinfunction "CATHODE_CATHODE") (pintype "passive"))
      (node (ref "U$39") (pin "2") (pinfunction "B_2") (pintype "passive"))
      (node (ref "U$39") (pin "5") (pinfunction "C1_5") (pintype "passive"))
    )
    (net (code "115") (name "Net-(U$39-E1)") (class "Default")
      (node (ref "D28") (pin "A") (pinfunction "A_A") (pintype "passive"))
      (node (ref "U$39") (pin "1") (pinfunction "E1_1") (pintype "passive"))
    )
    (net (code "116") (name "Net-(U$39-E2)") (class "Default")
      (node (ref "R81") (pin "1") (pinfunction "1_1") (pintype "passive"))
      (node (ref "U$39") (pin "3") (pinfunction "E2_3") (pintype "passive"))
    )
    (net (code "117") (name "Net-(U$40-B)") (class "Default")
      (node (ref "U$37") (pin "ANODE") (pinfunction "ANODE_ANODE") (pintype "passive"))
      (node (ref "U$40") (pin "2") (pinfunction "B_2") (pintype "passive"))
      (node (ref "U$40") (pin "5") (pinfunction "C1_5") (pintype "passive"))
    )
    (net (code "118") (name "Net-(U$40-E1)") (class "Default")
      (node (ref "D27") (pin "C") (pinfunction "C_C") (pintype "passive"))
      (node (ref "U$40") (pin "1") (pinfunction "E1_1") (pintype "passive"))
    )
    (net (code "119") (name "Net-(U$40-E2)") (class "Default")
      (node (ref "R79") (pin "2") (pinfunction "2_2") (pintype "passive"))
      (node (ref "U$40") (pin "3") (pinfunction "E2_3") (pintype "passive"))
    )
    (net (code "120") (name "Net-(VR1-A)") (class "Default")
      (node (ref "D1") (pin "A") (pinfunction "A_A") (pintype "passive"))
      (node (ref "VR1") (pin "1") (pinfunction "A_1") (pintype "passive"))
      (node (ref "VR1") (pin "2") (pinfunction "S_2") (pintype "passive"))
      (node (ref "VR4") (pin "2") (pinfunction "S_2") (pintype "passive"))
    )
    (net (code "121") (name "Net-(VR1-E)") (class "Default")
      (node (ref "D2") (pin "C") (pinfunction "C_C") (pintype "passive"))
      (node (ref "R7") (pin "1") (pinfunction "1_1") (pintype "passive"))
      (node (ref "R8") (pin "2") (pinfunction "2_2") (pintype "passive"))
      (node (ref "VR1") (pin "3") (pinfunction "E_3") (pintype "passive"))
    )
    (net (code "122") (name "Net-(VR2-E)") (class "Default")
      (node (ref "R5") (pin "2") (pinfunction "2_2") (pintype "passive"))
      (node (ref "VR2") (pin "3") (pinfunction "E_3") (pintype "passive"))
    )
    (net (code "123") (name "Net-(VR3-E)") (class "Default")
      (node (ref "R27") (pin "2") (pinfunction "2_2") (pintype "passive"))
      (node (ref "VR3") (pin "3") (pinfunction "E_3") (pintype "passive"))
    )
    (net (code "124") (name "OUT+") (class "Default")
      (node (ref "C14") (pin "2") (pinfunction "2_2") (pintype "passive"))
      (node (ref "D3") (pin "A") (pinfunction "A_A") (pintype "passive"))
      (node (ref "D4") (pin "C") (pinfunction "C_C") (pintype "passive"))
      (node (ref "R3") (pin "1") (pinfunction "1_1") (pintype "passive"))
      (node (ref "R31") (pin "2") (pinfunction "2_2") (pintype "passive"))
      (node (ref "R36") (pin "1") (pinfunction "1_1") (pintype "passive"))
      (node (ref "R48") (pin "1") (pinfunction "1_1") (pintype "passive"))
      (node (ref "TP2") (pin "TP") (pinfunction "TP_TP") (pintype "input"))
    )
    (net (code "125") (name "OUT-") (class "Default")
      (node (ref "C13") (pin "2") (pinfunction "2_2") (pintype "passive"))
      (node (ref "D10") (pin "C") (pinfunction "C_C") (pintype "passive"))
      (node (ref "D9") (pin "A") (pinfunction "A_A") (pintype "passive"))
      (node (ref "R34") (pin "2") (pinfunction "2_2") (pintype "passive"))
      (node (ref "R35") (pin "1") (pinfunction "1_1") (pintype "passive"))
      (node (ref "R4") (pin "2") (pinfunction "2_2") (pintype "passive"))
      (node (ref "R47") (pin "1") (pinfunction "1_1") (pintype "passive"))
      (node (ref "TP1") (pin "TP") (pinfunction "TP_TP") (pintype "input"))
    )
    (net (code "126") (name "V+REG") (class "Default")
      (node (ref "C15") (pin "1") (pinfunction "1_1") (pintype "passive"))
      (node (ref "C16") (pin "1") (pinfunction "1_1") (pintype "passive"))
      (node (ref "C20") (pin "+") (pinfunction "+_+") (pintype "passive"))
      (node (ref "CR1") (pin "ANODE") (pinfunction "ANODE_ANODE") (pintype "passive"))
      (node (ref "CR3") (pin "ANODE") (pinfunction "ANODE_ANODE") (pintype "passive"))
      (node (ref "LED5") (pin "A") (pinfunction "A_A") (pintype "passive"))
      (node (ref "R10") (pin "1") (pinfunction "1_1") (pintype "passive"))
      (node (ref "R14") (pin "1") (pinfunction "1_1") (pintype "passive"))
      (node (ref "R37") (pin "1") (pinfunction "1_1") (pintype "passive"))
      (node (ref "R38") (pin "1") (pinfunction "1_1") (pintype "passive"))
      (node (ref "R42") (pin "1") (pinfunction "1_1") (pintype "passive"))
      (node (ref "R9") (pin "1") (pinfunction "1_1") (pintype "passive"))
      (node (ref "U$19") (pin "P$3") (pinfunction "KL_P$3") (pintype "passive"))
    )
    (net (code "127") (name "V-REG") (class "Default")
      (node (ref "C17") (pin "2") (pinfunction "2_2") (pintype "passive"))
      (node (ref "C18") (pin "2") (pinfunction "2_2") (pintype "passive"))
      (node (ref "C19") (pin "-") (pinfunction "-_-") (pintype "passive"))
      (node (ref "CR2") (pin "CATHODE") (pinfunction "CATHODE_CATHODE") (pintype "passive"))
      (node (ref "CR4") (pin "CATHODE") (pinfunction "CATHODE_CATHODE") (pintype "passive"))
      (node (ref "LED6") (pin "C") (pinfunction "C_C") (pintype "passive"))
      (node (ref "R11") (pin "2") (pinfunction "2_2") (pintype "passive"))
      (node (ref "R12") (pin "2") (pinfunction "2_2") (pintype "passive"))
      (node (ref "R15") (pin "2") (pinfunction "2_2") (pintype "passive"))
      (node (ref "R39") (pin "2") (pinfunction "2_2") (pintype "passive"))
      (node (ref "R40") (pin "2") (pinfunction "2_2") (pintype "passive"))
      (node (ref "R44") (pin "2") (pinfunction "2_2") (pintype "passive"))
      (node (ref "U$19") (pin "P$5") (pinfunction "KL_P$5") (pintype "passive"))
    )
    (net (code "128") (name "V1+") (class "Default")
      (node (ref "C121") (pin "1") (pinfunction "1_1") (pintype "passive"))
      (node (ref "C25") (pin "1") (pinfunction "1_1") (pintype "passive"))
      (node (ref "C30") (pin "+") (pinfunction "+_+") (pintype "passive"))
      (node (ref "C32") (pin "+") (pinfunction "+_+") (pintype "passive"))
      (node (ref "C97") (pin "1") (pinfunction "1_1") (pintype "passive"))
      (node (ref "C99") (pin "1") (pinfunction "1_1") (pintype "passive"))
      (node (ref "CR7") (pin "CATHODE") (pinfunction "CATHODE_CATHODE") (pintype "passive"))
      (node (ref "D32") (pin "A") (pinfunction "A_A") (pintype "passive"))
      (node (ref "IC7") (pin "2") (pinfunction "IN_2") (pintype "input"))
      (node (ref "IC8") (pin "7") (pinfunction "V+_7") (pintype "power_in"))
      (node (ref "LED3") (pin "A") (pinfunction "A_A") (pintype "passive"))
      (node (ref "Q27") (pin "2") (pinfunction "D_2") (pintype "passive"))
      (node (ref "Q27") (pin "4") (pinfunction "D_4") (pintype "passive"))
      (node (ref "Q27") (pin "P$1") (pinfunction "D_P$1") (pintype "passive"))
      (node (ref "Q27") (pin "P$10") (pinfunction "D_P$10") (pintype "passive"))
      (node (ref "Q27") (pin "P$11") (pinfunction "D_P$11") (pintype "passive"))
      (node (ref "Q27") (pin "P$12") (pinfunction "D_P$12") (pintype "passive"))
      (node (ref "Q27") (pin "P$13") (pinfunction "D_P$13") (pintype "passive"))
      (node (ref "Q27") (pin "P$14") (pinfunction "D_P$14") (pintype "passive"))
      (node (ref "Q27") (pin "P$15") (pinfunction "D_P$15") (pintype "passive"))
      (node (ref "Q27") (pin "P$16") (pinfunction "D_P$16") (pintype "passive"))
      (node (ref "Q27") (pin "P$17") (pinfunction "D_P$17") (pintype "passive"))
      (node (ref "Q27") (pin "P$18") (pinfunction "D_P$18") (pintype "passive"))
      (node (ref "Q27") (pin "P$19") (pinfunction "D_P$19") (pintype "passive"))
      (node (ref "Q27") (pin "P$2") (pinfunction "D_P$2") (pintype "passive"))
      (node (ref "Q27") (pin "P$20") (pinfunction "D_P$20") (pintype "passive"))
      (node (ref "Q27") (pin "P$21") (pinfunction "D_P$21") (pintype "passive"))
      (node (ref "Q27") (pin "P$22") (pinfunction "D_P$22") (pintype "passive"))
      (node (ref "Q27") (pin "P$23") (pinfunction "D_P$23") (pintype "passive"))
      (node (ref "Q27") (pin "P$24") (pinfunction "D_P$24") (pintype "passive"))
      (node (ref "Q27") (pin "P$25") (pinfunction "D_P$25") (pintype "passive"))
      (node (ref "Q27") (pin "P$26") (pinfunction "D_P$26") (pintype "passive"))
      (node (ref "Q27") (pin "P$27") (pinfunction "D_P$27") (pintype "passive"))
      (node (ref "Q27") (pin "P$28") (pinfunction "D_P$28") (pintype "passive"))
      (node (ref "Q27") (pin "P$29") (pinfunction "D_P$29") (pintype "passive"))
      (node (ref "Q27") (pin "P$3") (pinfunction "D_P$3") (pintype "passive"))
      (node (ref "Q27") (pin "P$30") (pinfunction "D_P$30") (pintype "passive"))
      (node (ref "Q27") (pin "P$31") (pinfunction "D_P$31") (pintype "passive"))
      (node (ref "Q27") (pin "P$32") (pinfunction "D_P$32") (pintype "passive"))
      (node (ref "Q27") (pin "P$33") (pinfunction "D_P$33") (pintype "passive"))
      (node (ref "Q27") (pin "P$34") (pinfunction "D_P$34") (pintype "passive"))
      (node (ref "Q27") (pin "P$35") (pinfunction "D_P$35") (pintype "passive"))
      (node (ref "Q27") (pin "P$36") (pinfunction "D_P$36") (pintype "passive"))
      (node (ref "Q27") (pin "P$37") (pinfunction "D_P$37") (pintype "passive"))
      (node (ref "Q27") (pin "P$38") (pinfunction "D_P$38") (pintype "passive"))
      (node (ref "Q27") (pin "P$39") (pinfunction "D_P$39") (pintype "passive"))
      (node (ref "Q27") (pin "P$4") (pinfunction "D_P$4") (pintype "passive"))
      (node (ref "Q27") (pin "P$40") (pinfunction "D_P$40") (pintype "passive"))
      (node (ref "Q27") (pin "P$41") (pinfunction "D_P$41") (pintype "passive"))
      (node (ref "Q27") (pin "P$42") (pinfunction "D_P$42") (pintype "passive"))
      (node (ref "Q27") (pin "P$43") (pinfunction "D_P$43") (pintype "passive"))
      (node (ref "Q27") (pin "P$44") (pinfunction "D_P$44") (pintype "passive"))
      (node (ref "Q27") (pin "P$45") (pinfunction "D_P$45") (pintype "passive"))
      (node (ref "Q27") (pin "P$46") (pinfunction "D_P$46") (pintype "passive"))
      (node (ref "Q27") (pin "P$47") (pinfunction "D_P$47") (pintype "passive"))
      (node (ref "Q27") (pin "P$48") (pinfunction "D_P$48") (pintype "passive"))
      (node (ref "Q27") (pin "P$49") (pinfunction "D_P$49") (pintype "passive"))
      (node (ref "Q27") (pin "P$5") (pinfunction "D_P$5") (pintype "passive"))
      (node (ref "Q27") (pin "P$50") (pinfunction "D_P$50") (pintype "passive"))
      (node (ref "Q27") (pin "P$51") (pinfunction "D_P$51") (pintype "passive"))
      (node (ref "Q27") (pin "P$52") (pinfunction "D_P$52") (pintype "passive"))
      (node (ref "Q27") (pin "P$53") (pinfunction "D_P$53") (pintype "passive"))
      (node (ref "Q27") (pin "P$54") (pinfunction "D_P$54") (pintype "passive"))
      (node (ref "Q27") (pin "P$55") (pinfunction "D_P$55") (pintype "passive"))
      (node (ref "Q27") (pin "P$56") (pinfunction "D_P$56") (pintype "passive"))
      (node (ref "Q27") (pin "P$57") (pinfunction "D_P$57") (pintype "passive"))
      (node (ref "Q27") (pin "P$58") (pinfunction "D_P$58") (pintype "passive"))
      (node (ref "Q27") (pin "P$59") (pinfunction "D_P$59") (pintype "passive"))
      (node (ref "Q27") (pin "P$6") (pinfunction "D_P$6") (pintype "passive"))
      (node (ref "Q27") (pin "P$60") (pinfunction "D_P$60") (pintype "passive"))
      (node (ref "Q27") (pin "P$61") (pinfunction "D_P$61") (pintype "passive"))
      (node (ref "Q27") (pin "P$62") (pinfunction "D_P$62") (pintype "passive"))
      (node (ref "Q27") (pin "P$63") (pinfunction "D_P$63") (pintype "passive"))
      (node (ref "Q27") (pin "P$7") (pinfunction "D_P$7") (pintype "passive"))
      (node (ref "Q27") (pin "P$8") (pinfunction "D_P$8") (pintype "passive"))
      (node (ref "Q27") (pin "P$9") (pinfunction "D_P$9") (pintype "passive"))
      (node (ref "R6") (pin "2") (pinfunction "2_2") (pintype "passive"))
      (node (ref "R86") (pin "2") (pinfunction "2_2") (pintype "passive"))
      (node (ref "R88") (pin "2") (pinfunction "2_2") (pintype "passive"))
      (node (ref "U$35") (pin "3") (pinfunction "E_3") (pintype "passive"))
    )
    (net (code "129") (name "V1-") (class "Default")
      (node (ref "C119") (pin "2") (pinfunction "2_2") (pintype "passive"))
      (node (ref "C26") (pin "2") (pinfunction "2_2") (pintype "passive"))
      (node (ref "C31") (pin "-") (pinfunction "-_-") (pintype "passive"))
      (node (ref "C33") (pin "-") (pinfunction "-_-") (pintype "passive"))
      (node (ref "C98") (pin "2") (pinfunction "2_2") (pintype "passive"))
      (node (ref "CR8") (pin "CATHODE") (pinfunction "CATHODE_CATHODE") (pintype "passive"))
      (node (ref "D31") (pin "C") (pinfunction "C_C") (pintype "passive"))
      (node (ref "IC9") (pin "4") (pinfunction "V-_4") (pintype "power_in"))
      (node (ref "LED4") (pin "C") (pinfunction "C_C") (pintype "passive"))
      (node (ref "Q28") (pin "2") (pinfunction "D_2") (pintype "passive"))
      (node (ref "Q28") (pin "4") (pinfunction "D_4") (pintype "passive"))
      (node (ref "Q28") (pin "P$1") (pinfunction "D_P$1") (pintype "passive"))
      (node (ref "Q28") (pin "P$10") (pinfunction "D_P$10") (pintype "passive"))
      (node (ref "Q28") (pin "P$11") (pinfunction "D_P$11") (pintype "passive"))
      (node (ref "Q28") (pin "P$12") (pinfunction "D_P$12") (pintype "passive"))
      (node (ref "Q28") (pin "P$13") (pinfunction "D_P$13") (pintype "passive"))
      (node (ref "Q28") (pin "P$14") (pinfunction "D_P$14") (pintype "passive"))
      (node (ref "Q28") (pin "P$15") (pinfunction "D_P$15") (pintype "passive"))
      (node (ref "Q28") (pin "P$16") (pinfunction "D_P$16") (pintype "passive"))
      (node (ref "Q28") (pin "P$17") (pinfunction "D_P$17") (pintype "passive"))
      (node (ref "Q28") (pin "P$18") (pinfunction "D_P$18") (pintype "passive"))
      (node (ref "Q28") (pin "P$19") (pinfunction "D_P$19") (pintype "passive"))
      (node (ref "Q28") (pin "P$2") (pinfunction "D_P$2") (pintype "passive"))
      (node (ref "Q28") (pin "P$20") (pinfunction "D_P$20") (pintype "passive"))
      (node (ref "Q28") (pin "P$21") (pinfunction "D_P$21") (pintype "passive"))
      (node (ref "Q28") (pin "P$22") (pinfunction "D_P$22") (pintype "passive"))
      (node (ref "Q28") (pin "P$23") (pinfunction "D_P$23") (pintype "passive"))
      (node (ref "Q28") (pin "P$24") (pinfunction "D_P$24") (pintype "passive"))
      (node (ref "Q28") (pin "P$25") (pinfunction "D_P$25") (pintype "passive"))
      (node (ref "Q28") (pin "P$26") (pinfunction "D_P$26") (pintype "passive"))
      (node (ref "Q28") (pin "P$27") (pinfunction "D_P$27") (pintype "passive"))
      (node (ref "Q28") (pin "P$28") (pinfunction "D_P$28") (pintype "passive"))
      (node (ref "Q28") (pin "P$29") (pinfunction "D_P$29") (pintype "passive"))
      (node (ref "Q28") (pin "P$3") (pinfunction "D_P$3") (pintype "passive"))
      (node (ref "Q28") (pin "P$30") (pinfunction "D_P$30") (pintype "passive"))
      (node (ref "Q28") (pin "P$31") (pinfunction "D_P$31") (pintype "passive"))
      (node (ref "Q28") (pin "P$32") (pinfunction "D_P$32") (pintype "passive"))
      (node (ref "Q28") (pin "P$33") (pinfunction "D_P$33") (pintype "passive"))
      (node (ref "Q28") (pin "P$34") (pinfunction "D_P$34") (pintype "passive"))
      (node (ref "Q28") (pin "P$35") (pinfunction "D_P$35") (pintype "passive"))
      (node (ref "Q28") (pin "P$36") (pinfunction "D_P$36") (pintype "passive"))
      (node (ref "Q28") (pin "P$37") (pinfunction "D_P$37") (pintype "passive"))
      (node (ref "Q28") (pin "P$38") (pinfunction "D_P$38") (pintype "passive"))
      (node (ref "Q28") (pin "P$39") (pinfunction "D_P$39") (pintype "passive"))
      (node (ref "Q28") (pin "P$4") (pinfunction "D_P$4") (pintype "passive"))
      (node (ref "Q28") (pin "P$40") (pinfunction "D_P$40") (pintype "passive"))
      (node (ref "Q28") (pin "P$41") (pinfunction "D_P$41") (pintype "passive"))
      (node (ref "Q28") (pin "P$42") (pinfunction "D_P$42") (pintype "passive"))
      (node (ref "Q28") (pin "P$43") (pinfunction "D_P$43") (pintype "passive"))
      (node (ref "Q28") (pin "P$44") (pinfunction "D_P$44") (pintype "passive"))
      (node (ref "Q28") (pin "P$45") (pinfunction "D_P$45") (pintype "passive"))
      (node (ref "Q28") (pin "P$46") (pinfunction "D_P$46") (pintype "passive"))
      (node (ref "Q28") (pin "P$47") (pinfunction "D_P$47") (pintype "passive"))
      (node (ref "Q28") (pin "P$48") (pinfunction "D_P$48") (pintype "passive"))
      (node (ref "Q28") (pin "P$49") (pinfunction "D_P$49") (pintype "passive"))
      (node (ref "Q28") (pin "P$5") (pinfunction "D_P$5") (pintype "passive"))
      (node (ref "Q28") (pin "P$50") (pinfunction "D_P$50") (pintype "passive"))
      (node (ref "Q28") (pin "P$51") (pinfunction "D_P$51") (pintype "passive"))
      (node (ref "Q28") (pin "P$52") (pinfunction "D_P$52") (pintype "passive"))
      (node (ref "Q28") (pin "P$53") (pinfunction "D_P$53") (pintype "passive"))
      (node (ref "Q28") (pin "P$54") (pinfunction "D_P$54") (pintype "passive"))
      (node (ref "Q28") (pin "P$55") (pinfunction "D_P$55") (pintype "passive"))
      (node (ref "Q28") (pin "P$56") (pinfunction "D_P$56") (pintype "passive"))
      (node (ref "Q28") (pin "P$57") (pinfunction "D_P$57") (pintype "passive"))
      (node (ref "Q28") (pin "P$58") (pinfunction "D_P$58") (pintype "passive"))
      (node (ref "Q28") (pin "P$59") (pinfunction "D_P$59") (pintype "passive"))
      (node (ref "Q28") (pin "P$6") (pinfunction "D_P$6") (pintype "passive"))
      (node (ref "Q28") (pin "P$60") (pinfunction "D_P$60") (pintype "passive"))
      (node (ref "Q28") (pin "P$61") (pinfunction "D_P$61") (pintype "passive"))
      (node (ref "Q28") (pin "P$62") (pinfunction "D_P$62") (pintype "passive"))
      (node (ref "Q28") (pin "P$63") (pinfunction "D_P$63") (pintype "passive"))
      (node (ref "Q28") (pin "P$7") (pinfunction "D_P$7") (pintype "passive"))
      (node (ref "Q28") (pin "P$8") (pinfunction "D_P$8") (pintype "passive"))
      (node (ref "Q28") (pin "P$9") (pinfunction "D_P$9") (pintype "passive"))
      (node (ref "R13") (pin "2") (pinfunction "2_2") (pintype "passive"))
      (node (ref "R87") (pin "1") (pinfunction "1_1") (pintype "passive"))
      (node (ref "U$36") (pin "3") (pinfunction "E_3") (pintype "passive"))
    )
    (net (code "130") (name "V2+") (class "Default")
      (node (ref "C21") (pin "+") (pinfunction "+_+") (pintype "passive"))
      (node (ref "C23") (pin "+") (pinfunction "+_+") (pintype "passive"))
      (node (ref "C27") (pin "1") (pinfunction "1_1") (pintype "passive"))
      (node (ref "C70") (pin "1") (pinfunction "1_1") (pintype "passive"))
      (node (ref "C72") (pin "1") (pinfunction "1_1") (pintype "passive"))
      (node (ref "C94") (pin "1") (pinfunction "1_1") (pintype "passive"))
      (node (ref "CR10") (pin "ANODE") (pinfunction "ANODE_ANODE") (pintype "passive"))
      (node (ref "D25") (pin "A") (pinfunction "A_A") (pintype "passive"))
      (node (ref "IC4") (pin "2") (pinfunction "IN_2") (pintype "input"))
      (node (ref "IC5") (pin "7") (pinfunction "V+_7") (pintype "power_in"))
      (node (ref "LED1") (pin "A") (pinfunction "A_A") (pintype "passive"))
      (node (ref "Q23") (pin "2") (pinfunction "D_2") (pintype "passive"))
      (node (ref "Q23") (pin "4") (pinfunction "D_4") (pintype "passive"))
      (node (ref "Q23") (pin "P$1") (pinfunction "D_P$1") (pintype "passive"))
      (node (ref "Q23") (pin "P$10") (pinfunction "D_P$10") (pintype "passive"))
      (node (ref "Q23") (pin "P$11") (pinfunction "D_P$11") (pintype "passive"))
      (node (ref "Q23") (pin "P$12") (pinfunction "D_P$12") (pintype "passive"))
      (node (ref "Q23") (pin "P$13") (pinfunction "D_P$13") (pintype "passive"))
      (node (ref "Q23") (pin "P$14") (pinfunction "D_P$14") (pintype "passive"))
      (node (ref "Q23") (pin "P$15") (pinfunction "D_P$15") (pintype "passive"))
      (node (ref "Q23") (pin "P$16") (pinfunction "D_P$16") (pintype "passive"))
      (node (ref "Q23") (pin "P$17") (pinfunction "D_P$17") (pintype "passive"))
      (node (ref "Q23") (pin "P$18") (pinfunction "D_P$18") (pintype "passive"))
      (node (ref "Q23") (pin "P$19") (pinfunction "D_P$19") (pintype "passive"))
      (node (ref "Q23") (pin "P$2") (pinfunction "D_P$2") (pintype "passive"))
      (node (ref "Q23") (pin "P$20") (pinfunction "D_P$20") (pintype "passive"))
      (node (ref "Q23") (pin "P$21") (pinfunction "D_P$21") (pintype "passive"))
      (node (ref "Q23") (pin "P$22") (pinfunction "D_P$22") (pintype "passive"))
      (node (ref "Q23") (pin "P$23") (pinfunction "D_P$23") (pintype "passive"))
      (node (ref "Q23") (pin "P$24") (pinfunction "D_P$24") (pintype "passive"))
      (node (ref "Q23") (pin "P$25") (pinfunction "D_P$25") (pintype "passive"))
      (node (ref "Q23") (pin "P$26") (pinfunction "D_P$26") (pintype "passive"))
      (node (ref "Q23") (pin "P$27") (pinfunction "D_P$27") (pintype "passive"))
      (node (ref "Q23") (pin "P$28") (pinfunction "D_P$28") (pintype "passive"))
      (node (ref "Q23") (pin "P$29") (pinfunction "D_P$29") (pintype "passive"))
      (node (ref "Q23") (pin "P$3") (pinfunction "D_P$3") (pintype "passive"))
      (node (ref "Q23") (pin "P$30") (pinfunction "D_P$30") (pintype "passive"))
      (node (ref "Q23") (pin "P$31") (pinfunction "D_P$31") (pintype "passive"))
      (node (ref "Q23") (pin "P$32") (pinfunction "D_P$32") (pintype "passive"))
      (node (ref "Q23") (pin "P$33") (pinfunction "D_P$33") (pintype "passive"))
      (node (ref "Q23") (pin "P$34") (pinfunction "D_P$34") (pintype "passive"))
      (node (ref "Q23") (pin "P$35") (pinfunction "D_P$35") (pintype "passive"))
      (node (ref "Q23") (pin "P$36") (pinfunction "D_P$36") (pintype "passive"))
      (node (ref "Q23") (pin "P$37") (pinfunction "D_P$37") (pintype "passive"))
      (node (ref "Q23") (pin "P$38") (pinfunction "D_P$38") (pintype "passive"))
      (node (ref "Q23") (pin "P$39") (pinfunction "D_P$39") (pintype "passive"))
      (node (ref "Q23") (pin "P$4") (pinfunction "D_P$4") (pintype "passive"))
      (node (ref "Q23") (pin "P$40") (pinfunction "D_P$40") (pintype "passive"))
      (node (ref "Q23") (pin "P$41") (pinfunction "D_P$41") (pintype "passive"))
      (node (ref "Q23") (pin "P$42") (pinfunction "D_P$42") (pintype "passive"))
      (node (ref "Q23") (pin "P$43") (pinfunction "D_P$43") (pintype "passive"))
      (node (ref "Q23") (pin "P$44") (pinfunction "D_P$44") (pintype "passive"))
      (node (ref "Q23") (pin "P$45") (pinfunction "D_P$45") (pintype "passive"))
      (node (ref "Q23") (pin "P$46") (pinfunction "D_P$46") (pintype "passive"))
      (node (ref "Q23") (pin "P$47") (pinfunction "D_P$47") (pintype "passive"))
      (node (ref "Q23") (pin "P$48") (pinfunction "D_P$48") (pintype "passive"))
      (node (ref "Q23") (pin "P$49") (pinfunction "D_P$49") (pintype "passive"))
      (node (ref "Q23") (pin "P$5") (pinfunction "D_P$5") (pintype "passive"))
      (node (ref "Q23") (pin "P$50") (pinfunction "D_P$50") (pintype "passive"))
      (node (ref "Q23") (pin "P$51") (pinfunction "D_P$51") (pintype "passive"))
      (node (ref "Q23") (pin "P$52") (pinfunction "D_P$52") (pintype "passive"))
      (node (ref "Q23") (pin "P$53") (pinfunction "D_P$53") (pintype "passive"))
      (node (ref "Q23") (pin "P$54") (pinfunction "D_P$54") (pintype "passive"))
      (node (ref "Q23") (pin "P$55") (pinfunction "D_P$55") (pintype "passive"))
      (node (ref "Q23") (pin "P$56") (pinfunction "D_P$56") (pintype "passive"))
      (node (ref "Q23") (pin "P$57") (pinfunction "D_P$57") (pintype "passive"))
      (node (ref "Q23") (pin "P$58") (pinfunction "D_P$58") (pintype "passive"))
      (node (ref "Q23") (pin "P$59") (pinfunction "D_P$59") (pintype "passive"))
      (node (ref "Q23") (pin "P$6") (pinfunction "D_P$6") (pintype "passive"))
      (node (ref "Q23") (pin "P$60") (pinfunction "D_P$60") (pintype "passive"))
      (node (ref "Q23") (pin "P$61") (pinfunction "D_P$61") (pintype "passive"))
      (node (ref "Q23") (pin "P$62") (pinfunction "D_P$62") (pintype "passive"))
      (node (ref "Q23") (pin "P$63") (pinfunction "D_P$63") (pintype "passive"))
      (node (ref "Q23") (pin "P$7") (pinfunction "D_P$7") (pintype "passive"))
      (node (ref "Q23") (pin "P$8") (pinfunction "D_P$8") (pintype "passive"))
      (node (ref "Q23") (pin "P$9") (pinfunction "D_P$9") (pintype "passive"))
      (node (ref "R28") (pin "2") (pinfunction "2_2") (pintype "passive"))
      (node (ref "R74") (pin "2") (pinfunction "2_2") (pintype "passive"))
      (node (ref "R76") (pin "2") (pinfunction "2_2") (pintype "passive"))
      (node (ref "U$27") (pin "3") (pinfunction "E_3") (pintype "passive"))
    )
    (net (code "131") (name "V2-") (class "Default")
      (node (ref "C22") (pin "-") (pinfunction "-_-") (pintype "passive"))
      (node (ref "C24") (pin "-") (pinfunction "-_-") (pintype "passive"))
      (node (ref "C28") (pin "2") (pinfunction "2_2") (pintype "passive"))
      (node (ref "C71") (pin "2") (pinfunction "2_2") (pintype "passive"))
      (node (ref "C92") (pin "2") (pinfunction "2_2") (pintype "passive"))
      (node (ref "CR9") (pin "CATHODE") (pinfunction "CATHODE_CATHODE") (pintype "passive"))
      (node (ref "D24") (pin "C") (pinfunction "C_C") (pintype "passive"))
      (node (ref "IC6") (pin "4") (pinfunction "V-_4") (pintype "power_in"))
      (node (ref "LED2") (pin "C") (pinfunction "C_C") (pintype "passive"))
      (node (ref "Q24") (pin "2") (pinfunction "D_2") (pintype "passive"))
      (node (ref "Q24") (pin "4") (pinfunction "D_4") (pintype "passive"))
      (node (ref "Q24") (pin "P$1") (pinfunction "D_P$1") (pintype "passive"))
      (node (ref "Q24") (pin "P$10") (pinfunction "D_P$10") (pintype "passive"))
      (node (ref "Q24") (pin "P$11") (pinfunction "D_P$11") (pintype "passive"))
      (node (ref "Q24") (pin "P$12") (pinfunction "D_P$12") (pintype "passive"))
      (node (ref "Q24") (pin "P$13") (pinfunction "D_P$13") (pintype "passive"))
      (node (ref "Q24") (pin "P$14") (pinfunction "D_P$14") (pintype "passive"))
      (node (ref "Q24") (pin "P$15") (pinfunction "D_P$15") (pintype "passive"))
      (node (ref "Q24") (pin "P$16") (pinfunction "D_P$16") (pintype "passive"))
      (node (ref "Q24") (pin "P$17") (pinfunction "D_P$17") (pintype "passive"))
      (node (ref "Q24") (pin "P$18") (pinfunction "D_P$18") (pintype "passive"))
      (node (ref "Q24") (pin "P$19") (pinfunction "D_P$19") (pintype "passive"))
      (node (ref "Q24") (pin "P$2") (pinfunction "D_P$2") (pintype "passive"))
      (node (ref "Q24") (pin "P$20") (pinfunction "D_P$20") (pintype "passive"))
      (node (ref "Q24") (pin "P$21") (pinfunction "D_P$21") (pintype "passive"))
      (node (ref "Q24") (pin "P$22") (pinfunction "D_P$22") (pintype "passive"))
      (node (ref "Q24") (pin "P$23") (pinfunction "D_P$23") (pintype "passive"))
      (node (ref "Q24") (pin "P$24") (pinfunction "D_P$24") (pintype "passive"))
      (node (ref "Q24") (pin "P$25") (pinfunction "D_P$25") (pintype "passive"))
      (node (ref "Q24") (pin "P$26") (pinfunction "D_P$26") (pintype "passive"))
      (node (ref "Q24") (pin "P$27") (pinfunction "D_P$27") (pintype "passive"))
      (node (ref "Q24") (pin "P$28") (pinfunction "D_P$28") (pintype "passive"))
      (node (ref "Q24") (pin "P$29") (pinfunction "D_P$29") (pintype "passive"))
      (node (ref "Q24") (pin "P$3") (pinfunction "D_P$3") (pintype "passive"))
      (node (ref "Q24") (pin "P$30") (pinfunction "D_P$30") (pintype "passive"))
      (node (ref "Q24") (pin "P$31") (pinfunction "D_P$31") (pintype "passive"))
      (node (ref "Q24") (pin "P$32") (pinfunction "D_P$32") (pintype "passive"))
      (node (ref "Q24") (pin "P$33") (pinfunction "D_P$33") (pintype "passive"))
      (node (ref "Q24") (pin "P$34") (pinfunction "D_P$34") (pintype "passive"))
      (node (ref "Q24") (pin "P$35") (pinfunction "D_P$35") (pintype "passive"))
      (node (ref "Q24") (pin "P$36") (pinfunction "D_P$36") (pintype "passive"))
      (node (ref "Q24") (pin "P$37") (pinfunction "D_P$37") (pintype "passive"))
      (node (ref "Q24") (pin "P$38") (pinfunction "D_P$38") (pintype "passive"))
      (node (ref "Q24") (pin "P$39") (pinfunction "D_P$39") (pintype "passive"))
      (node (ref "Q24") (pin "P$4") (pinfunction "D_P$4") (pintype "passive"))
      (node (ref "Q24") (pin "P$40") (pinfunction "D_P$40") (pintype "passive"))
      (node (ref "Q24") (pin "P$41") (pinfunction "D_P$41") (pintype "passive"))
      (node (ref "Q24") (pin "P$42") (pinfunction "D_P$42") (pintype "passive"))
      (node (ref "Q24") (pin "P$43") (pinfunction "D_P$43") (pintype "passive"))
      (node (ref "Q24") (pin "P$44") (pinfunction "D_P$44") (pintype "passive"))
      (node (ref "Q24") (pin "P$45") (pinfunction "D_P$45") (pintype "passive"))
      (node (ref "Q24") (pin "P$46") (pinfunction "D_P$46") (pintype "passive"))
      (node (ref "Q24") (pin "P$47") (pinfunction "D_P$47") (pintype "passive"))
      (node (ref "Q24") (pin "P$48") (pinfunction "D_P$48") (pintype "passive"))
      (node (ref "Q24") (pin "P$49") (pinfunction "D_P$49") (pintype "passive"))
      (node (ref "Q24") (pin "P$5") (pinfunction "D_P$5") (pintype "passive"))
      (node (ref "Q24") (pin "P$50") (pinfunction "D_P$50") (pintype "passive"))
      (node (ref "Q24") (pin "P$51") (pinfunction "D_P$51") (pintype "passive"))
      (node (ref "Q24") (pin "P$52") (pinfunction "D_P$52") (pintype "passive"))
      (node (ref "Q24") (pin "P$53") (pinfunction "D_P$53") (pintype "passive"))
      (node (ref "Q24") (pin "P$54") (pinfunction "D_P$54") (pintype "passive"))
      (node (ref "Q24") (pin "P$55") (pinfunction "D_P$55") (pintype "passive"))
      (node (ref "Q24") (pin "P$56") (pinfunction "D_P$56") (pintype "passive"))
      (node (ref "Q24") (pin "P$57") (pinfunction "D_P$57") (pintype "passive"))
      (node (ref "Q24") (pin "P$58") (pinfunction "D_P$58") (pintype "passive"))
      (node (ref "Q24") (pin "P$59") (pinfunction "D_P$59") (pintype "passive"))
      (node (ref "Q24") (pin "P$6") (pinfunction "D_P$6") (pintype "passive"))
      (node (ref "Q24") (pin "P$60") (pinfunction "D_P$60") (pintype "passive"))
      (node (ref "Q24") (pin "P$61") (pinfunction "D_P$61") (pintype "passive"))
      (node (ref "Q24") (pin "P$62") (pinfunction "D_P$62") (pintype "passive"))
      (node (ref "Q24") (pin "P$63") (pinfunction "D_P$63") (pintype "passive"))
      (node (ref "Q24") (pin "P$7") (pinfunction "D_P$7") (pintype "passive"))
      (node (ref "Q24") (pin "P$8") (pinfunction "D_P$8") (pintype "passive"))
      (node (ref "Q24") (pin "P$9") (pinfunction "D_P$9") (pintype "passive"))
      (node (ref "R29") (pin "2") (pinfunction "2_2") (pintype "passive"))
      (node (ref "R75") (pin "1") (pinfunction "1_1") (pintype "passive"))
      (node (ref "U$28") (pin "3") (pinfunction "E_3") (pintype "passive"))
    )
    (net (code "132") (name "VIN+") (class "Default")
      (node (ref "C111") (pin "+") (pinfunction "+_+") (pintype "passive"))
      (node (ref "C113") (pin "+") (pinfunction "+_+") (pintype "passive"))
      (node (ref "D27") (pin "A") (pinfunction "A_A") (pintype "passive"))
      (node (ref "D32") (pin "C") (pinfunction "C_C") (pintype "passive"))
      (node (ref "R79") (pin "1") (pinfunction "1_1") (pintype "passive"))
      (node (ref "U$35") (pin "2") (pinfunction "C_2") (pintype "passive"))
      (node (ref "U$35") (pin "4") (pinfunction "C_4") (pintype "passive"))
      (node (ref "U$35") (pin "P$1") (pinfunction "C_P$1") (pintype "passive"))
      (node (ref "U$35") (pin "P$10") (pinfunction "C_P$10") (pintype "passive"))
      (node (ref "U$35") (pin "P$11") (pinfunction "C_P$11") (pintype "passive"))
      (node (ref "U$35") (pin "P$12") (pinfunction "C_P$12") (pintype "passive"))
      (node (ref "U$35") (pin "P$13") (pinfunction "C_P$13") (pintype "passive"))
      (node (ref "U$35") (pin "P$14") (pinfunction "C_P$14") (pintype "passive"))
      (node (ref "U$35") (pin "P$15") (pinfunction "C_P$15") (pintype "passive"))
      (node (ref "U$35") (pin "P$16") (pinfunction "C_P$16") (pintype "passive"))
      (node (ref "U$35") (pin "P$17") (pinfunction "C_P$17") (pintype "passive"))
      (node (ref "U$35") (pin "P$18") (pinfunction "C_P$18") (pintype "passive"))
      (node (ref "U$35") (pin "P$19") (pinfunction "C_P$19") (pintype "passive"))
      (node (ref "U$35") (pin "P$2") (pinfunction "C_P$2") (pintype "passive"))
      (node (ref "U$35") (pin "P$20") (pinfunction "C_P$20") (pintype "passive"))
      (node (ref "U$35") (pin "P$21") (pinfunction "C_P$21") (pintype "passive"))
      (node (ref "U$35") (pin "P$22") (pinfunction "C_P$22") (pintype "passive"))
      (node (ref "U$35") (pin "P$23") (pinfunction "C_P$23") (pintype "passive"))
      (node (ref "U$35") (pin "P$24") (pinfunction "C_P$24") (pintype "passive"))
      (node (ref "U$35") (pin "P$25") (pinfunction "C_P$25") (pintype "passive"))
      (node (ref "U$35") (pin "P$26") (pinfunction "C_P$26") (pintype "passive"))
      (node (ref "U$35") (pin "P$27") (pinfunction "C_P$27") (pintype "passive"))
      (node (ref "U$35") (pin "P$28") (pinfunction "C_P$28") (pintype "passive"))
      (node (ref "U$35") (pin "P$29") (pinfunction "C_P$29") (pintype "passive"))
      (node (ref "U$35") (pin "P$3") (pinfunction "C_P$3") (pintype "passive"))
      (node (ref "U$35") (pin "P$30") (pinfunction "C_P$30") (pintype "passive"))
      (node (ref "U$35") (pin "P$31") (pinfunction "C_P$31") (pintype "passive"))
      (node (ref "U$35") (pin "P$32") (pinfunction "C_P$32") (pintype "passive"))
      (node (ref "U$35") (pin "P$33") (pinfunction "C_P$33") (pintype "passive"))
      (node (ref "U$35") (pin "P$34") (pinfunction "C_P$34") (pintype "passive"))
      (node (ref "U$35") (pin "P$35") (pinfunction "C_P$35") (pintype "passive"))
      (node (ref "U$35") (pin "P$36") (pinfunction "C_P$36") (pintype "passive"))
      (node (ref "U$35") (pin "P$37") (pinfunction "C_P$37") (pintype "passive"))
      (node (ref "U$35") (pin "P$38") (pinfunction "C_P$38") (pintype "passive"))
      (node (ref "U$35") (pin "P$39") (pinfunction "C_P$39") (pintype "passive"))
      (node (ref "U$35") (pin "P$4") (pinfunction "C_P$4") (pintype "passive"))
      (node (ref "U$35") (pin "P$40") (pinfunction "C_P$40") (pintype "passive"))
      (node (ref "U$35") (pin "P$41") (pinfunction "C_P$41") (pintype "passive"))
      (node (ref "U$35") (pin "P$42") (pinfunction "C_P$42") (pintype "passive"))
      (node (ref "U$35") (pin "P$43") (pinfunction "C_P$43") (pintype "passive"))
      (node (ref "U$35") (pin "P$44") (pinfunction "C_P$44") (pintype "passive"))
      (node (ref "U$35") (pin "P$45") (pinfunction "C_P$45") (pintype "passive"))
      (node (ref "U$35") (pin "P$46") (pinfunction "C_P$46") (pintype "passive"))
      (node (ref "U$35") (pin "P$47") (pinfunction "C_P$47") (pintype "passive"))
      (node (ref "U$35") (pin "P$48") (pinfunction "C_P$48") (pintype "passive"))
      (node (ref "U$35") (pin "P$49") (pinfunction "C_P$49") (pintype "passive"))
      (node (ref "U$35") (pin "P$5") (pinfunction "C_P$5") (pintype "passive"))
      (node (ref "U$35") (pin "P$50") (pinfunction "C_P$50") (pintype "passive"))
      (node (ref "U$35") (pin "P$51") (pinfunction "C_P$51") (pintype "passive"))
      (node (ref "U$35") (pin "P$52") (pinfunction "C_P$52") (pintype "passive"))
      (node (ref "U$35") (pin "P$53") (pinfunction "C_P$53") (pintype "passive"))
      (node (ref "U$35") (pin "P$54") (pinfunction "C_P$54") (pintype "passive"))
      (node (ref "U$35") (pin "P$55") (pinfunction "C_P$55") (pintype "passive"))
      (node (ref "U$35") (pin "P$56") (pinfunction "C_P$56") (pintype "passive"))
      (node (ref "U$35") (pin "P$57") (pinfunction "C_P$57") (pintype "passive"))
      (node (ref "U$35") (pin "P$58") (pinfunction "C_P$58") (pintype "passive"))
      (node (ref "U$35") (pin "P$59") (pinfunction "C_P$59") (pintype "passive"))
      (node (ref "U$35") (pin "P$6") (pinfunction "C_P$6") (pintype "passive"))
      (node (ref "U$35") (pin "P$60") (pinfunction "C_P$60") (pintype "passive"))
      (node (ref "U$35") (pin "P$61") (pinfunction "C_P$61") (pintype "passive"))
      (node (ref "U$35") (pin "P$62") (pinfunction "C_P$62") (pintype "passive"))
      (node (ref "U$35") (pin "P$63") (pinfunction "C_P$63") (pintype "passive"))
      (node (ref "U$35") (pin "P$7") (pinfunction "C_P$7") (pintype "passive"))
      (node (ref "U$35") (pin "P$8") (pinfunction "C_P$8") (pintype "passive"))
      (node (ref "U$35") (pin "P$9") (pinfunction "C_P$9") (pintype "passive"))
      (node (ref "U$41") (pin "P$5") (pinfunction "KL_P$5") (pintype "passive"))
    )
    (net (code "133") (name "VIN-") (class "Default")
      (node (ref "C112") (pin "-") (pinfunction "-_-") (pintype "passive"))
      (node (ref "C114") (pin "-") (pinfunction "-_-") (pintype "passive"))
      (node (ref "D28") (pin "C") (pinfunction "C_C") (pintype "passive"))
      (node (ref "D31") (pin "A") (pinfunction "A_A") (pintype "passive"))
      (node (ref "R81") (pin "2") (pinfunction "2_2") (pintype "passive"))
      (node (ref "U$36") (pin "2") (pinfunction "C_2") (pintype "passive"))
      (node (ref "U$36") (pin "4") (pinfunction "C_4") (pintype "passive"))
      (node (ref "U$36") (pin "P$1") (pinfunction "C_P$1") (pintype "passive"))
      (node (ref "U$36") (pin "P$10") (pinfunction "C_P$10") (pintype "passive"))
      (node (ref "U$36") (pin "P$11") (pinfunction "C_P$11") (pintype "passive"))
      (node (ref "U$36") (pin "P$12") (pinfunction "C_P$12") (pintype "passive"))
      (node (ref "U$36") (pin "P$13") (pinfunction "C_P$13") (pintype "passive"))
      (node (ref "U$36") (pin "P$14") (pinfunction "C_P$14") (pintype "passive"))
      (node (ref "U$36") (pin "P$15") (pinfunction "C_P$15") (pintype "passive"))
      (node (ref "U$36") (pin "P$16") (pinfunction "C_P$16") (pintype "passive"))
      (node (ref "U$36") (pin "P$17") (pinfunction "C_P$17") (pintype "passive"))
      (node (ref "U$36") (pin "P$18") (pinfunction "C_P$18") (pintype "passive"))
      (node (ref "U$36") (pin "P$19") (pinfunction "C_P$19") (pintype "passive"))
      (node (ref "U$36") (pin "P$2") (pinfunction "C_P$2") (pintype "passive"))
      (node (ref "U$36") (pin "P$20") (pinfunction "C_P$20") (pintype "passive"))
      (node (ref "U$36") (pin "P$21") (pinfunction "C_P$21") (pintype "passive"))
      (node (ref "U$36") (pin "P$22") (pinfunction "C_P$22") (pintype "passive"))
      (node (ref "U$36") (pin "P$23") (pinfunction "C_P$23") (pintype "passive"))
      (node (ref "U$36") (pin "P$24") (pinfunction "C_P$24") (pintype "passive"))
      (node (ref "U$36") (pin "P$25") (pinfunction "C_P$25") (pintype "passive"))
      (node (ref "U$36") (pin "P$26") (pinfunction "C_P$26") (pintype "passive"))
      (node (ref "U$36") (pin "P$27") (pinfunction "C_P$27") (pintype "passive"))
      (node (ref "U$36") (pin "P$28") (pinfunction "C_P$28") (pintype "passive"))
      (node (ref "U$36") (pin "P$29") (pinfunction "C_P$29") (pintype "passive"))
      (node (ref "U$36") (pin "P$3") (pinfunction "C_P$3") (pintype "passive"))
      (node (ref "U$36") (pin "P$30") (pinfunction "C_P$30") (pintype "passive"))
      (node (ref "U$36") (pin "P$31") (pinfunction "C_P$31") (pintype "passive"))
      (node (ref "U$36") (pin "P$32") (pinfunction "C_P$32") (pintype "passive"))
      (node (ref "U$36") (pin "P$33") (pinfunction "C_P$33") (pintype "passive"))
      (node (ref "U$36") (pin "P$34") (pinfunction "C_P$34") (pintype "passive"))
      (node (ref "U$36") (pin "P$35") (pinfunction "C_P$35") (pintype "passive"))
      (node (ref "U$36") (pin "P$36") (pinfunction "C_P$36") (pintype "passive"))
      (node (ref "U$36") (pin "P$37") (pinfunction "C_P$37") (pintype "passive"))
      (node (ref "U$36") (pin "P$38") (pinfunction "C_P$38") (pintype "passive"))
      (node (ref "U$36") (pin "P$39") (pinfunction "C_P$39") (pintype "passive"))
      (node (ref "U$36") (pin "P$4") (pinfunction "C_P$4") (pintype "passive"))
      (node (ref "U$36") (pin "P$40") (pinfunction "C_P$40") (pintype "passive"))
      (node (ref "U$36") (pin "P$41") (pinfunction "C_P$41") (pintype "passive"))
      (node (ref "U$36") (pin "P$42") (pinfunction "C_P$42") (pintype "passive"))
      (node (ref "U$36") (pin "P$43") (pinfunction "C_P$43") (pintype "passive"))
      (node (ref "U$36") (pin "P$44") (pinfunction "C_P$44") (pintype "passive"))
      (node (ref "U$36") (pin "P$45") (pinfunction "C_P$45") (pintype "passive"))
      (node (ref "U$36") (pin "P$46") (pinfunction "C_P$46") (pintype "passive"))
      (node (ref "U$36") (pin "P$47") (pinfunction "C_P$47") (pintype "passive"))
      (node (ref "U$36") (pin "P$48") (pinfunction "C_P$48") (pintype "passive"))
      (node (ref "U$36") (pin "P$49") (pinfunction "C_P$49") (pintype "passive"))
      (node (ref "U$36") (pin "P$5") (pinfunction "C_P$5") (pintype "passive"))
      (node (ref "U$36") (pin "P$50") (pinfunction "C_P$50") (pintype "passive"))
      (node (ref "U$36") (pin "P$51") (pinfunction "C_P$51") (pintype "passive"))
      (node (ref "U$36") (pin "P$52") (pinfunction "C_P$52") (pintype "passive"))
      (node (ref "U$36") (pin "P$53") (pinfunction "C_P$53") (pintype "passive"))
      (node (ref "U$36") (pin "P$54") (pinfunction "C_P$54") (pintype "passive"))
      (node (ref "U$36") (pin "P$55") (pinfunction "C_P$55") (pintype "passive"))
      (node (ref "U$36") (pin "P$56") (pinfunction "C_P$56") (pintype "passive"))
      (node (ref "U$36") (pin "P$57") (pinfunction "C_P$57") (pintype "passive"))
      (node (ref "U$36") (pin "P$58") (pinfunction "C_P$58") (pintype "passive"))
      (node (ref "U$36") (pin "P$59") (pinfunction "C_P$59") (pintype "passive"))
      (node (ref "U$36") (pin "P$6") (pinfunction "C_P$6") (pintype "passive"))
      (node (ref "U$36") (pin "P$60") (pinfunction "C_P$60") (pintype "passive"))
      (node (ref "U$36") (pin "P$61") (pinfunction "C_P$61") (pintype "passive"))
      (node (ref "U$36") (pin "P$62") (pinfunction "C_P$62") (pintype "passive"))
      (node (ref "U$36") (pin "P$63") (pinfunction "C_P$63") (pintype "passive"))
      (node (ref "U$36") (pin "P$7") (pinfunction "C_P$7") (pintype "passive"))
      (node (ref "U$36") (pin "P$8") (pinfunction "C_P$8") (pintype "passive"))
      (node (ref "U$36") (pin "P$9") (pinfunction "C_P$9") (pintype "passive"))
      (node (ref "U$41") (pin "P$3") (pinfunction "KL_P$3") (pintype "passive"))
    )
    (net (code "134") (name "VIN2+") (class "Default")
      (node (ref "C84") (pin "+") (pinfunction "+_+") (pintype "passive"))
      (node (ref "C86") (pin "+") (pinfunction "+_+") (pintype "passive"))
      (node (ref "D20") (pin "A") (pinfunction "A_A") (pintype "passive"))
      (node (ref "D25") (pin "C") (pinfunction "C_C") (pintype "passive"))
      (node (ref "R67") (pin "1") (pinfunction "1_1") (pintype "passive"))
      (node (ref "U$27") (pin "2") (pinfunction "C_2") (pintype "passive"))
      (node (ref "U$27") (pin "4") (pinfunction "C_4") (pintype "passive"))
      (node (ref "U$27") (pin "P$1") (pinfunction "C_P$1") (pintype "passive"))
      (node (ref "U$27") (pin "P$10") (pinfunction "C_P$10") (pintype "passive"))
      (node (ref "U$27") (pin "P$11") (pinfunction "C_P$11") (pintype "passive"))
      (node (ref "U$27") (pin "P$12") (pinfunction "C_P$12") (pintype "passive"))
      (node (ref "U$27") (pin "P$13") (pinfunction "C_P$13") (pintype "passive"))
      (node (ref "U$27") (pin "P$14") (pinfunction "C_P$14") (pintype "passive"))
      (node (ref "U$27") (pin "P$15") (pinfunction "C_P$15") (pintype "passive"))
      (node (ref "U$27") (pin "P$16") (pinfunction "C_P$16") (pintype "passive"))
      (node (ref "U$27") (pin "P$17") (pinfunction "C_P$17") (pintype "passive"))
      (node (ref "U$27") (pin "P$18") (pinfunction "C_P$18") (pintype "passive"))
      (node (ref "U$27") (pin "P$19") (pinfunction "C_P$19") (pintype "passive"))
      (node (ref "U$27") (pin "P$2") (pinfunction "C_P$2") (pintype "passive"))
      (node (ref "U$27") (pin "P$20") (pinfunction "C_P$20") (pintype "passive"))
      (node (ref "U$27") (pin "P$21") (pinfunction "C_P$21") (pintype "passive"))
      (node (ref "U$27") (pin "P$22") (pinfunction "C_P$22") (pintype "passive"))
      (node (ref "U$27") (pin "P$23") (pinfunction "C_P$23") (pintype "passive"))
      (node (ref "U$27") (pin "P$24") (pinfunction "C_P$24") (pintype "passive"))
      (node (ref "U$27") (pin "P$25") (pinfunction "C_P$25") (pintype "passive"))
      (node (ref "U$27") (pin "P$26") (pinfunction "C_P$26") (pintype "passive"))
      (node (ref "U$27") (pin "P$27") (pinfunction "C_P$27") (pintype "passive"))
      (node (ref "U$27") (pin "P$28") (pinfunction "C_P$28") (pintype "passive"))
      (node (ref "U$27") (pin "P$29") (pinfunction "C_P$29") (pintype "passive"))
      (node (ref "U$27") (pin "P$3") (pinfunction "C_P$3") (pintype "passive"))
      (node (ref "U$27") (pin "P$30") (pinfunction "C_P$30") (pintype "passive"))
      (node (ref "U$27") (pin "P$31") (pinfunction "C_P$31") (pintype "passive"))
      (node (ref "U$27") (pin "P$32") (pinfunction "C_P$32") (pintype "passive"))
      (node (ref "U$27") (pin "P$33") (pinfunction "C_P$33") (pintype "passive"))
      (node (ref "U$27") (pin "P$34") (pinfunction "C_P$34") (pintype "passive"))
      (node (ref "U$27") (pin "P$35") (pinfunction "C_P$35") (pintype "passive"))
      (node (ref "U$27") (pin "P$36") (pinfunction "C_P$36") (pintype "passive"))
      (node (ref "U$27") (pin "P$37") (pinfunction "C_P$37") (pintype "passive"))
      (node (ref "U$27") (pin "P$38") (pinfunction "C_P$38") (pintype "passive"))
      (node (ref "U$27") (pin "P$39") (pinfunction "C_P$39") (pintype "passive"))
      (node (ref "U$27") (pin "P$4") (pinfunction "C_P$4") (pintype "passive"))
      (node (ref "U$27") (pin "P$40") (pinfunction "C_P$40") (pintype "passive"))
      (node (ref "U$27") (pin "P$41") (pinfunction "C_P$41") (pintype "passive"))
      (node (ref "U$27") (pin "P$42") (pinfunction "C_P$42") (pintype "passive"))
      (node (ref "U$27") (pin "P$43") (pinfunction "C_P$43") (pintype "passive"))
      (node (ref "U$27") (pin "P$44") (pinfunction "C_P$44") (pintype "passive"))
      (node (ref "U$27") (pin "P$45") (pinfunction "C_P$45") (pintype "passive"))
      (node (ref "U$27") (pin "P$46") (pinfunction "C_P$46") (pintype "passive"))
      (node (ref "U$27") (pin "P$47") (pinfunction "C_P$47") (pintype "passive"))
      (node (ref "U$27") (pin "P$48") (pinfunction "C_P$48") (pintype "passive"))
      (node (ref "U$27") (pin "P$49") (pinfunction "C_P$49") (pintype "passive"))
      (node (ref "U$27") (pin "P$5") (pinfunction "C_P$5") (pintype "passive"))
      (node (ref "U$27") (pin "P$50") (pinfunction "C_P$50") (pintype "passive"))
      (node (ref "U$27") (pin "P$51") (pinfunction "C_P$51") (pintype "passive"))
      (node (ref "U$27") (pin "P$52") (pinfunction "C_P$52") (pintype "passive"))
      (node (ref "U$27") (pin "P$53") (pinfunction "C_P$53") (pintype "passive"))
      (node (ref "U$27") (pin "P$54") (pinfunction "C_P$54") (pintype "passive"))
      (node (ref "U$27") (pin "P$55") (pinfunction "C_P$55") (pintype "passive"))
      (node (ref "U$27") (pin "P$56") (pinfunction "C_P$56") (pintype "passive"))
      (node (ref "U$27") (pin "P$57") (pinfunction "C_P$57") (pintype "passive"))
      (node (ref "U$27") (pin "P$58") (pinfunction "C_P$58") (pintype "passive"))
      (node (ref "U$27") (pin "P$59") (pinfunction "C_P$59") (pintype "passive"))
      (node (ref "U$27") (pin "P$6") (pinfunction "C_P$6") (pintype "passive"))
      (node (ref "U$27") (pin "P$60") (pinfunction "C_P$60") (pintype "passive"))
      (node (ref "U$27") (pin "P$61") (pinfunction "C_P$61") (pintype "passive"))
      (node (ref "U$27") (pin "P$62") (pinfunction "C_P$62") (pintype "passive"))
      (node (ref "U$27") (pin "P$63") (pinfunction "C_P$63") (pintype "passive"))
      (node (ref "U$27") (pin "P$7") (pinfunction "C_P$7") (pintype "passive"))
      (node (ref "U$27") (pin "P$8") (pinfunction "C_P$8") (pintype "passive"))
      (node (ref "U$27") (pin "P$9") (pinfunction "C_P$9") (pintype "passive"))
      (node (ref "U$33") (pin "P$3") (pinfunction "KL_P$3") (pintype "passive"))
    )
    (net (code "135") (name "VIN2-") (class "Default")
      (node (ref "C85") (pin "-") (pinfunction "-_-") (pintype "passive"))
      (node (ref "C87") (pin "-") (pinfunction "-_-") (pintype "passive"))
      (node (ref "D21") (pin "C") (pinfunction "C_C") (pintype "passive"))
      (node (ref "D24") (pin "A") (pinfunction "A_A") (pintype "passive"))
      (node (ref "R69") (pin "2") (pinfunction "2_2") (pintype "passive"))
      (node (ref "U$28") (pin "2") (pinfunction "C_2") (pintype "passive"))
      (node (ref "U$28") (pin "4") (pinfunction "C_4") (pintype "passive"))
      (node (ref "U$28") (pin "P$1") (pinfunction "C_P$1") (pintype "passive"))
      (node (ref "U$28") (pin "P$10") (pinfunction "C_P$10") (pintype "passive"))
      (node (ref "U$28") (pin "P$11") (pinfunction "C_P$11") (pintype "passive"))
      (node (ref "U$28") (pin "P$12") (pinfunction "C_P$12") (pintype "passive"))
      (node (ref "U$28") (pin "P$13") (pinfunction "C_P$13") (pintype "passive"))
      (node (ref "U$28") (pin "P$14") (pinfunction "C_P$14") (pintype "passive"))
      (node (ref "U$28") (pin "P$15") (pinfunction "C_P$15") (pintype "passive"))
      (node (ref "U$28") (pin "P$16") (pinfunction "C_P$16") (pintype "passive"))
      (node (ref "U$28") (pin "P$17") (pinfunction "C_P$17") (pintype "passive"))
      (node (ref "U$28") (pin "P$18") (pinfunction "C_P$18") (pintype "passive"))
      (node (ref "U$28") (pin "P$19") (pinfunction "C_P$19") (pintype "passive"))
      (node (ref "U$28") (pin "P$2") (pinfunction "C_P$2") (pintype "passive"))
      (node (ref "U$28") (pin "P$20") (pinfunction "C_P$20") (pintype "passive"))
      (node (ref "U$28") (pin "P$21") (pinfunction "C_P$21") (pintype "passive"))
      (node (ref "U$28") (pin "P$22") (pinfunction "C_P$22") (pintype "passive"))
      (node (ref "U$28") (pin "P$23") (pinfunction "C_P$23") (pintype "passive"))
      (node (ref "U$28") (pin "P$24") (pinfunction "C_P$24") (pintype "passive"))
      (node (ref "U$28") (pin "P$25") (pinfunction "C_P$25") (pintype "passive"))
      (node (ref "U$28") (pin "P$26") (pinfunction "C_P$26") (pintype "passive"))
      (node (ref "U$28") (pin "P$27") (pinfunction "C_P$27") (pintype "passive"))
      (node (ref "U$28") (pin "P$28") (pinfunction "C_P$28") (pintype "passive"))
      (node (ref "U$28") (pin "P$29") (pinfunction "C_P$29") (pintype "passive"))
      (node (ref "U$28") (pin "P$3") (pinfunction "C_P$3") (pintype "passive"))
      (node (ref "U$28") (pin "P$30") (pinfunction "C_P$30") (pintype "passive"))
      (node (ref "U$28") (pin "P$31") (pinfunction "C_P$31") (pintype "passive"))
      (node (ref "U$28") (pin "P$32") (pinfunction "C_P$32") (pintype "passive"))
      (node (ref "U$28") (pin "P$33") (pinfunction "C_P$33") (pintype "passive"))
      (node (ref "U$28") (pin "P$34") (pinfunction "C_P$34") (pintype "passive"))
      (node (ref "U$28") (pin "P$35") (pinfunction "C_P$35") (pintype "passive"))
      (node (ref "U$28") (pin "P$36") (pinfunction "C_P$36") (pintype "passive"))
      (node (ref "U$28") (pin "P$37") (pinfunction "C_P$37") (pintype "passive"))
      (node (ref "U$28") (pin "P$38") (pinfunction "C_P$38") (pintype "passive"))
      (node (ref "U$28") (pin "P$39") (pinfunction "C_P$39") (pintype "passive"))
      (node (ref "U$28") (pin "P$4") (pinfunction "C_P$4") (pintype "passive"))
      (node (ref "U$28") (pin "P$40") (pinfunction "C_P$40") (pintype "passive"))
      (node (ref "U$28") (pin "P$41") (pinfunction "C_P$41") (pintype "passive"))
      (node (ref "U$28") (pin "P$42") (pinfunction "C_P$42") (pintype "passive"))
      (node (ref "U$28") (pin "P$43") (pinfunction "C_P$43") (pintype "passive"))
      (node (ref "U$28") (pin "P$44") (pinfunction "C_P$44") (pintype "passive"))
      (node (ref "U$28") (pin "P$45") (pinfunction "C_P$45") (pintype "passive"))
      (node (ref "U$28") (pin "P$46") (pinfunction "C_P$46") (pintype "passive"))
      (node (ref "U$28") (pin "P$47") (pinfunction "C_P$47") (pintype "passive"))
      (node (ref "U$28") (pin "P$48") (pinfunction "C_P$48") (pintype "passive"))
      (node (ref "U$28") (pin "P$49") (pinfunction "C_P$49") (pintype "passive"))
      (node (ref "U$28") (pin "P$5") (pinfunction "C_P$5") (pintype "passive"))
      (node (ref "U$28") (pin "P$50") (pinfunction "C_P$50") (pintype "passive"))
      (node (ref "U$28") (pin "P$51") (pinfunction "C_P$51") (pintype "passive"))
      (node (ref "U$28") (pin "P$52") (pinfunction "C_P$52") (pintype "passive"))
      (node (ref "U$28") (pin "P$53") (pinfunction "C_P$53") (pintype "passive"))
      (node (ref "U$28") (pin "P$54") (pinfunction "C_P$54") (pintype "passive"))
      (node (ref "U$28") (pin "P$55") (pinfunction "C_P$55") (pintype "passive"))
      (node (ref "U$28") (pin "P$56") (pinfunction "C_P$56") (pintype "passive"))
      (node (ref "U$28") (pin "P$57") (pinfunction "C_P$57") (pintype "passive"))
      (node (ref "U$28") (pin "P$58") (pinfunction "C_P$58") (pintype "passive"))
      (node (ref "U$28") (pin "P$59") (pinfunction "C_P$59") (pintype "passive"))
      (node (ref "U$28") (pin "P$6") (pinfunction "C_P$6") (pintype "passive"))
      (node (ref "U$28") (pin "P$60") (pinfunction "C_P$60") (pintype "passive"))
      (node (ref "U$28") (pin "P$61") (pinfunction "C_P$61") (pintype "passive"))
      (node (ref "U$28") (pin "P$62") (pinfunction "C_P$62") (pintype "passive"))
      (node (ref "U$28") (pin "P$63") (pinfunction "C_P$63") (pintype "passive"))
      (node (ref "U$28") (pin "P$7") (pinfunction "C_P$7") (pintype "passive"))
      (node (ref "U$28") (pin "P$8") (pinfunction "C_P$8") (pintype "passive"))
      (node (ref "U$28") (pin "P$9") (pinfunction "C_P$9") (pintype "passive"))
      (node (ref "U$33") (pin "P$5") (pinfunction "KL_P$5") (pintype "passive"))
    )
    (net (code "136") (name "unconnected-(IC5-CMP1-Pad1)") (class "Default")
      (node (ref "IC5") (pin "1") (pinfunction "CMP1_1") (pintype "passive"))
    )
    (net (code "137") (name "unconnected-(IC5-CMP2-Pad8)") (class "Default")
      (node (ref "IC5") (pin "8") (pinfunction "CMP2_8") (pintype "passive"))
    )
    (net (code "138") (name "unconnected-(IC6-CMP1-Pad1)") (class "Default")
      (node (ref "IC6") (pin "1") (pinfunction "CMP1_1") (pintype "passive"))
    )
    (net (code "139") (name "unconnected-(IC6-CMP2-Pad8)") (class "Default")
      (node (ref "IC6") (pin "8") (pinfunction "CMP2_8") (pintype "passive"))
    )
    (net (code "140") (name "unconnected-(IC8-CMP1-Pad1)") (class "Default")
      (node (ref "IC8") (pin "1") (pinfunction "CMP1_1") (pintype "passive"))
    )
    (net (code "141") (name "unconnected-(IC8-CMP2-Pad8)") (class "Default")
      (node (ref "IC8") (pin "8") (pinfunction "CMP2_8") (pintype "passive"))
    )
    (net (code "142") (name "unconnected-(IC9-CMP1-Pad1)") (class "Default")
      (node (ref "IC9") (pin "1") (pinfunction "CMP1_1") (pintype "passive"))
    )
    (net (code "143") (name "unconnected-(IC9-CMP2-Pad8)") (class "Default")
      (node (ref "IC9") (pin "8") (pinfunction "CMP2_8") (pintype "passive"))
    )
    (net (code "144") (name "unconnected-(U$4-E-Pad2)") (class "Default")
      (node (ref "U$4") (pin "2") (pinfunction "E_2") (pintype "passive"))
    )
    (net (code "145") (name "unconnected-(U$16-E-Pad2)") (class "Default")
      (node (ref "U$16") (pin "2") (pinfunction "E_2") (pintype "passive"))
    )
  )
)
